# Rear_Logic.net
KiCad netlist of a schematic drawn in EAGLE
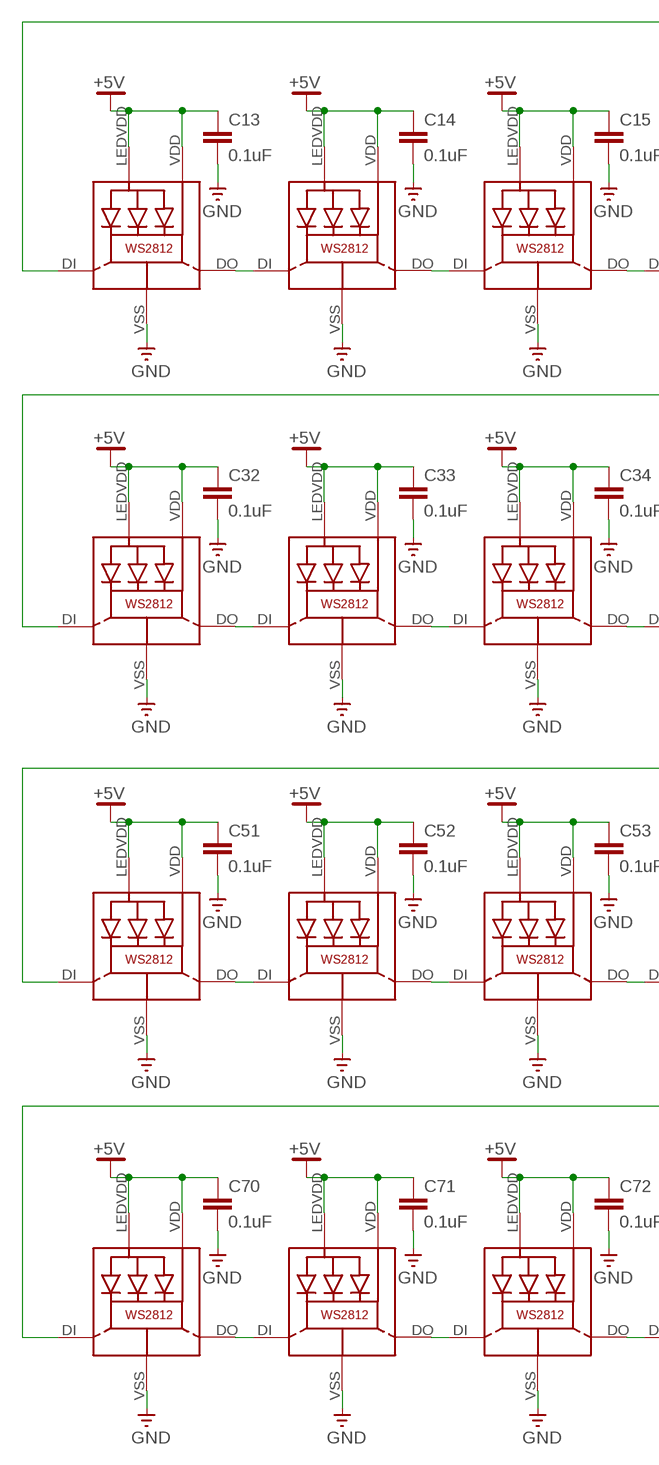
[diagram p0: schematic, sheet 1, part 1 of 2]
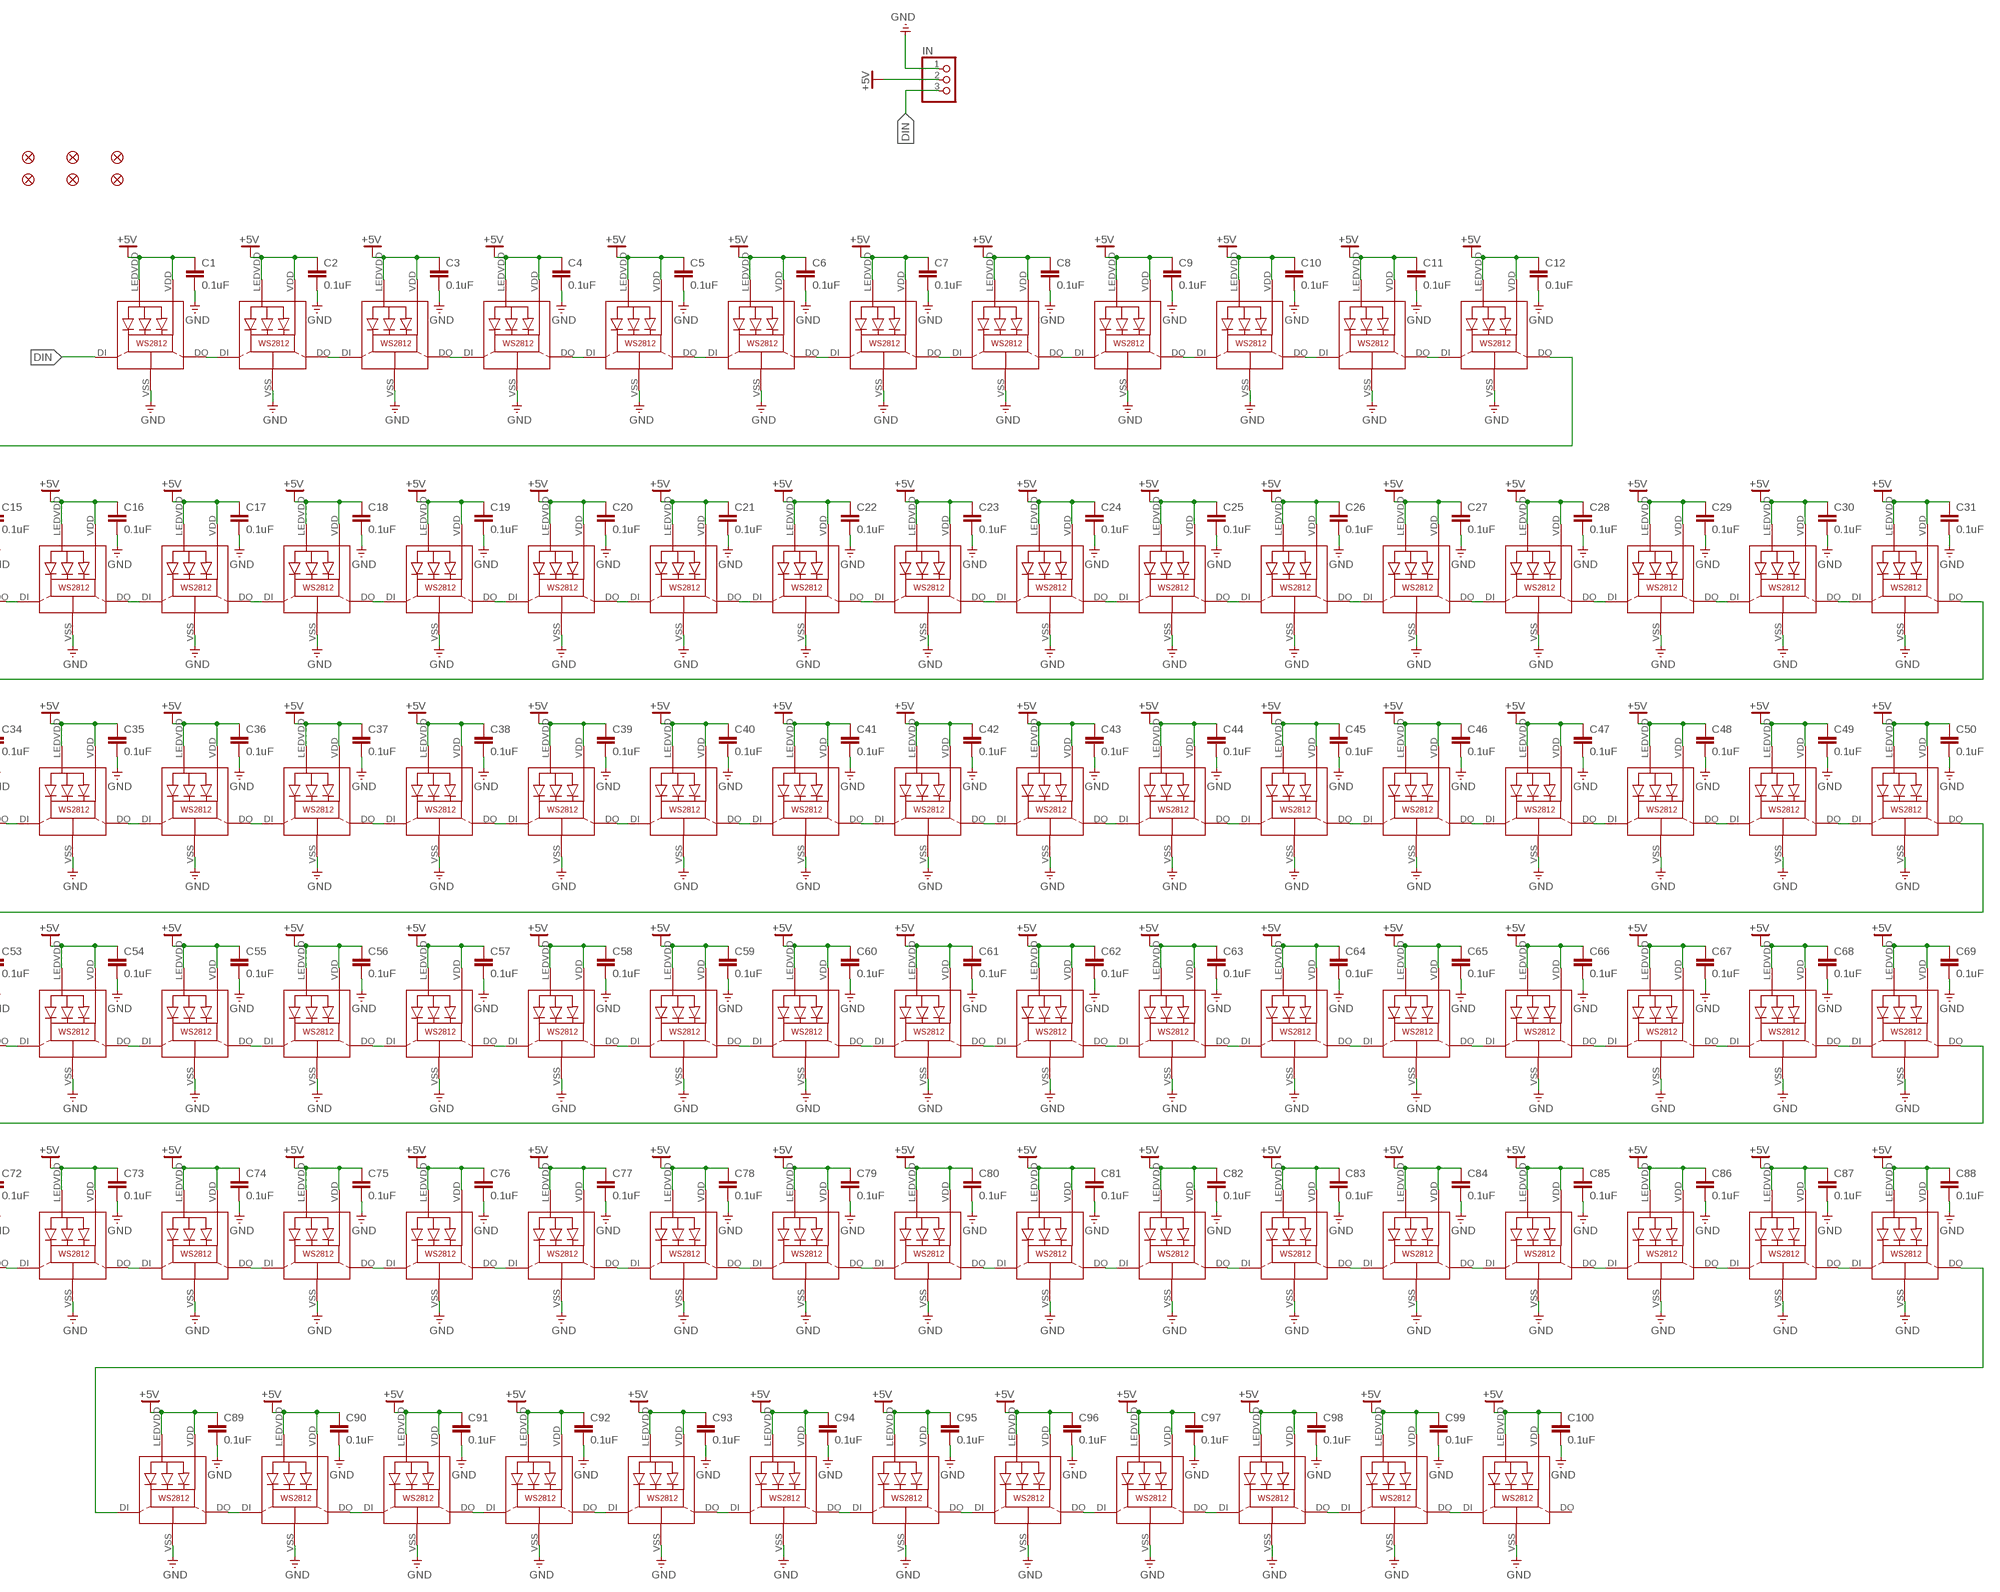
[diagram p1: schematic, sheet 1, part 2 of 2]

(export (version "E")
  (design (tool "Eeschema 10.0.6"))
  (components
    (comp (ref "C1")
      (value "0.1uF")
      (footprint "eagle-import:0805")
      (libsource (lib "eagle-import") (part "CAP0805"))
    )
    (comp (ref "C2")
      (value "0.1uF")
      (footprint "eagle-import:0805")
      (libsource (lib "eagle-import") (part "CAP0805"))
    )
    (comp (ref "C3")
      (value "0.1uF")
      (footprint "eagle-import:0805")
      (libsource (lib "eagle-import") (part "CAP0805"))
    )
    (comp (ref "C4")
      (value "0.1uF")
      (footprint "eagle-import:0805")
      (libsource (lib "eagle-import") (part "CAP0805"))
    )
    (comp (ref "C5")
      (value "0.1uF")
      (footprint "eagle-import:0805")
      (libsource (lib "eagle-import") (part "CAP0805"))
    )
    (comp (ref "C6")
      (value "0.1uF")
      (footprint "eagle-import:0805")
      (libsource (lib "eagle-import") (part "CAP0805"))
    )
    (comp (ref "C7")
      (value "0.1uF")
      (footprint "eagle-import:0805")
      (libsource (lib "eagle-import") (part "CAP0805"))
    )
    (comp (ref "C8")
      (value "0.1uF")
      (footprint "eagle-import:0805")
      (libsource (lib "eagle-import") (part "CAP0805"))
    )
    (comp (ref "C9")
      (value "0.1uF")
      (footprint "eagle-import:0805")
      (libsource (lib "eagle-import") (part "CAP0805"))
    )
    (comp (ref "C10")
      (value "0.1uF")
      (footprint "eagle-import:0805")
      (libsource (lib "eagle-import") (part "CAP0805"))
    )
    (comp (ref "C11")
      (value "0.1uF")
      (footprint "eagle-import:0805")
      (libsource (lib "eagle-import") (part "CAP0805"))
    )
    (comp (ref "C12")
      (value "0.1uF")
      (footprint "eagle-import:0805")
      (libsource (lib "eagle-import") (part "CAP0805"))
    )
    (comp (ref "C13")
      (value "0.1uF")
      (footprint "eagle-import:0805")
      (libsource (lib "eagle-import") (part "CAP0805"))
    )
    (comp (ref "C14")
      (value "0.1uF")
      (footprint "eagle-import:0805")
      (libsource (lib "eagle-import") (part "CAP0805"))
    )
    (comp (ref "C15")
      (value "0.1uF")
      (footprint "eagle-import:0805")
      (libsource (lib "eagle-import") (part "CAP0805"))
    )
    (comp (ref "C16")
      (value "0.1uF")
      (footprint "eagle-import:0805")
      (libsource (lib "eagle-import") (part "CAP0805"))
    )
    (comp (ref "C17")
      (value "0.1uF")
      (footprint "eagle-import:0805")
      (libsource (lib "eagle-import") (part "CAP0805"))
    )
    (comp (ref "C18")
      (value "0.1uF")
      (footprint "eagle-import:0805")
      (libsource (lib "eagle-import") (part "CAP0805"))
    )
    (comp (ref "C19")
      (value "0.1uF")
      (footprint "eagle-import:0805")
      (libsource (lib "eagle-import") (part "CAP0805"))
    )
    (comp (ref "C20")
      (value "0.1uF")
      (footprint "eagle-import:0805")
      (libsource (lib "eagle-import") (part "CAP0805"))
    )
    (comp (ref "C21")
      (value "0.1uF")
      (footprint "eagle-import:0805")
      (libsource (lib "eagle-import") (part "CAP0805"))
    )
    (comp (ref "C22")
      (value "0.1uF")
      (footprint "eagle-import:0805")
      (libsource (lib "eagle-import") (part "CAP0805"))
    )
    (comp (ref "C23")
      (value "0.1uF")
      (footprint "eagle-import:0805")
      (libsource (lib "eagle-import") (part "CAP0805"))
    )
    (comp (ref "C24")
      (value "0.1uF")
      (footprint "eagle-import:0805")
      (libsource (lib "eagle-import") (part "CAP0805"))
    )
    (comp (ref "C25")
      (value "0.1uF")
      (footprint "eagle-import:0805")
      (libsource (lib "eagle-import") (part "CAP0805"))
    )
    (comp (ref "C26")
      (value "0.1uF")
      (footprint "eagle-import:0805")
      (libsource (lib "eagle-import") (part "CAP0805"))
    )
    (comp (ref "C27")
      (value "0.1uF")
      (footprint "eagle-import:0805")
      (libsource (lib "eagle-import") (part "CAP0805"))
    )
    (comp (ref "C28")
      (value "0.1uF")
      (footprint "eagle-import:0805")
      (libsource (lib "eagle-import") (part "CAP0805"))
    )
    (comp (ref "C29")
      (value "0.1uF")
      (footprint "eagle-import:0805")
      (libsource (lib "eagle-import") (part "CAP0805"))
    )
    (comp (ref "C30")
      (value "0.1uF")
      (footprint "eagle-import:0805")
      (libsource (lib "eagle-import") (part "CAP0805"))
    )
    (comp (ref "C31")
      (value "0.1uF")
      (footprint "eagle-import:0805")
      (libsource (lib "eagle-import") (part "CAP0805"))
    )
    (comp (ref "C32")
      (value "0.1uF")
      (footprint "eagle-import:0805")
      (libsource (lib "eagle-import") (part "CAP0805"))
    )
    (comp (ref "C33")
      (value "0.1uF")
      (footprint "eagle-import:0805")
      (libsource (lib "eagle-import") (part "CAP0805"))
    )
    (comp (ref "C34")
      (value "0.1uF")
      (footprint "eagle-import:0805")
      (libsource (lib "eagle-import") (part "CAP0805"))
    )
    (comp (ref "C35")
      (value "0.1uF")
      (footprint "eagle-import:0805")
      (libsource (lib "eagle-import") (part "CAP0805"))
    )
    (comp (ref "C36")
      (value "0.1uF")
      (footprint "eagle-import:0805")
      (libsource (lib "eagle-import") (part "CAP0805"))
    )
    (comp (ref "C37")
      (value "0.1uF")
      (footprint "eagle-import:0805")
      (libsource (lib "eagle-import") (part "CAP0805"))
    )
    (comp (ref "C38")
      (value "0.1uF")
      (footprint "eagle-import:0805")
      (libsource (lib "eagle-import") (part "CAP0805"))
    )
    (comp (ref "C39")
      (value "0.1uF")
      (footprint "eagle-import:0805")
      (libsource (lib "eagle-import") (part "CAP0805"))
    )
    (comp (ref "C40")
      (value "0.1uF")
      (footprint "eagle-import:0805")
      (libsource (lib "eagle-import") (part "CAP0805"))
    )
    (comp (ref "C41")
      (value "0.1uF")
      (footprint "eagle-import:0805")
      (libsource (lib "eagle-import") (part "CAP0805"))
    )
    (comp (ref "C42")
      (value "0.1uF")
      (footprint "eagle-import:0805")
      (libsource (lib "eagle-import") (part "CAP0805"))
    )
    (comp (ref "C43")
      (value "0.1uF")
      (footprint "eagle-import:0805")
      (libsource (lib "eagle-import") (part "CAP0805"))
    )
    (comp (ref "C44")
      (value "0.1uF")
      (footprint "eagle-import:0805")
      (libsource (lib "eagle-import") (part "CAP0805"))
    )
    (comp (ref "C45")
      (value "0.1uF")
      (footprint "eagle-import:0805")
      (libsource (lib "eagle-import") (part "CAP0805"))
    )
    (comp (ref "C46")
      (value "0.1uF")
      (footprint "eagle-import:0805")
      (libsource (lib "eagle-import") (part "CAP0805"))
    )
    (comp (ref "C47")
      (value "0.1uF")
      (footprint "eagle-import:0805")
      (libsource (lib "eagle-import") (part "CAP0805"))
    )
    (comp (ref "C48")
      (value "0.1uF")
      (footprint "eagle-import:0805")
      (libsource (lib "eagle-import") (part "CAP0805"))
    )
    (comp (ref "C49")
      (value "0.1uF")
      (footprint "eagle-import:0805")
      (libsource (lib "eagle-import") (part "CAP0805"))
    )
    (comp (ref "C50")
      (value "0.1uF")
      (footprint "eagle-import:0805")
      (libsource (lib "eagle-import") (part "CAP0805"))
    )
    (comp (ref "C51")
      (value "0.1uF")
      (footprint "eagle-import:0805")
      (libsource (lib "eagle-import") (part "CAP0805"))
    )
    (comp (ref "C52")
      (value "0.1uF")
      (footprint "eagle-import:0805")
      (libsource (lib "eagle-import") (part "CAP0805"))
    )
    (comp (ref "C53")
      (value "0.1uF")
      (footprint "eagle-import:0805")
      (libsource (lib "eagle-import") (part "CAP0805"))
    )
    (comp (ref "C54")
      (value "0.1uF")
      (footprint "eagle-import:0805")
      (libsource (lib "eagle-import") (part "CAP0805"))
    )
    (comp (ref "C55")
      (value "0.1uF")
      (footprint "eagle-import:0805")
      (libsource (lib "eagle-import") (part "CAP0805"))
    )
    (comp (ref "C56")
      (value "0.1uF")
      (footprint "eagle-import:0805")
      (libsource (lib "eagle-import") (part "CAP0805"))
    )
    (comp (ref "C57")
      (value "0.1uF")
      (footprint "eagle-import:0805")
      (libsource (lib "eagle-import") (part "CAP0805"))
    )
    (comp (ref "C58")
      (value "0.1uF")
      (footprint "eagle-import:0805")
      (libsource (lib "eagle-import") (part "CAP0805"))
    )
    (comp (ref "C59")
      (value "0.1uF")
      (footprint "eagle-import:0805")
      (libsource (lib "eagle-import") (part "CAP0805"))
    )
    (comp (ref "C60")
      (value "0.1uF")
      (footprint "eagle-import:0805")
      (libsource (lib "eagle-import") (part "CAP0805"))
    )
    (comp (ref "C61")
      (value "0.1uF")
      (footprint "eagle-import:0805")
      (libsource (lib "eagle-import") (part "CAP0805"))
    )
    (comp (ref "C62")
      (value "0.1uF")
      (footprint "eagle-import:0805")
      (libsource (lib "eagle-import") (part "CAP0805"))
    )
    (comp (ref "C63")
      (value "0.1uF")
      (footprint "eagle-import:0805")
      (libsource (lib "eagle-import") (part "CAP0805"))
    )
    (comp (ref "C64")
      (value "0.1uF")
      (footprint "eagle-import:0805")
      (libsource (lib "eagle-import") (part "CAP0805"))
    )
    (comp (ref "C65")
      (value "0.1uF")
      (footprint "eagle-import:0805")
      (libsource (lib "eagle-import") (part "CAP0805"))
    )
    (comp (ref "C66")
      (value "0.1uF")
      (footprint "eagle-import:0805")
      (libsource (lib "eagle-import") (part "CAP0805"))
    )
    (comp (ref "C67")
      (value "0.1uF")
      (footprint "eagle-import:0805")
      (libsource (lib "eagle-import") (part "CAP0805"))
    )
    (comp (ref "C68")
      (value "0.1uF")
      (footprint "eagle-import:0805")
      (libsource (lib "eagle-import") (part "CAP0805"))
    )
    (comp (ref "C69")
      (value "0.1uF")
      (footprint "eagle-import:0805")
      (libsource (lib "eagle-import") (part "CAP0805"))
    )
    (comp (ref "C70")
      (value "0.1uF")
      (footprint "eagle-import:0805")
      (libsource (lib "eagle-import") (part "CAP0805"))
    )
    (comp (ref "C71")
      (value "0.1uF")
      (footprint "eagle-import:0805")
      (libsource (lib "eagle-import") (part "CAP0805"))
    )
    (comp (ref "C72")
      (value "0.1uF")
      (footprint "eagle-import:0805")
      (libsource (lib "eagle-import") (part "CAP0805"))
    )
    (comp (ref "C73")
      (value "0.1uF")
      (footprint "eagle-import:0805")
      (libsource (lib "eagle-import") (part "CAP0805"))
    )
    (comp (ref "C74")
      (value "0.1uF")
      (footprint "eagle-import:0805")
      (libsource (lib "eagle-import") (part "CAP0805"))
    )
    (comp (ref "C75")
      (value "0.1uF")
      (footprint "eagle-import:0805")
      (libsource (lib "eagle-import") (part "CAP0805"))
    )
    (comp (ref "C76")
      (value "0.1uF")
      (footprint "eagle-import:0805")
      (libsource (lib "eagle-import") (part "CAP0805"))
    )
    (comp (ref "C77")
      (value "0.1uF")
      (footprint "eagle-import:0805")
      (libsource (lib "eagle-import") (part "CAP0805"))
    )
    (comp (ref "C78")
      (value "0.1uF")
      (footprint "eagle-import:0805")
      (libsource (lib "eagle-import") (part "CAP0805"))
    )
    (comp (ref "C79")
      (value "0.1uF")
      (footprint "eagle-import:0805")
      (libsource (lib "eagle-import") (part "CAP0805"))
    )
    (comp (ref "C80")
      (value "0.1uF")
      (footprint "eagle-import:0805")
      (libsource (lib "eagle-import") (part "CAP0805"))
    )
    (comp (ref "C81")
      (value "0.1uF")
      (footprint "eagle-import:0805")
      (libsource (lib "eagle-import") (part "CAP0805"))
    )
    (comp (ref "C82")
      (value "0.1uF")
      (footprint "eagle-import:0805")
      (libsource (lib "eagle-import") (part "CAP0805"))
    )
    (comp (ref "C83")
      (value "0.1uF")
      (footprint "eagle-import:0805")
      (libsource (lib "eagle-import") (part "CAP0805"))
    )
    (comp (ref "C84")
      (value "0.1uF")
      (footprint "eagle-import:0805")
      (libsource (lib "eagle-import") (part "CAP0805"))
    )
    (comp (ref "C85")
      (value "0.1uF")
      (footprint "eagle-import:0805")
      (libsource (lib "eagle-import") (part "CAP0805"))
    )
    (comp (ref "C86")
      (value "0.1uF")
      (footprint "eagle-import:0805")
      (libsource (lib "eagle-import") (part "CAP0805"))
    )
    (comp (ref "C87")
      (value "0.1uF")
      (footprint "eagle-import:0805")
      (libsource (lib "eagle-import") (part "CAP0805"))
    )
    (comp (ref "C88")
      (value "0.1uF")
      (footprint "eagle-import:0805")
      (libsource (lib "eagle-import") (part "CAP0805"))
    )
    (comp (ref "C89")
      (value "0.1uF")
      (footprint "eagle-import:0805")
      (libsource (lib "eagle-import") (part "CAP0805"))
    )
    (comp (ref "C90")
      (value "0.1uF")
      (footprint "eagle-import:0805")
      (libsource (lib "eagle-import") (part "CAP0805"))
    )
    (comp (ref "C91")
      (value "0.1uF")
      (footprint "eagle-import:0805")
      (libsource (lib "eagle-import") (part "CAP0805"))
    )
    (comp (ref "C92")
      (value "0.1uF")
      (footprint "eagle-import:0805")
      (libsource (lib "eagle-import") (part "CAP0805"))
    )
    (comp (ref "C93")
      (value "0.1uF")
      (footprint "eagle-import:0805")
      (libsource (lib "eagle-import") (part "CAP0805"))
    )
    (comp (ref "C94")
      (value "0.1uF")
      (footprint "eagle-import:0805")
      (libsource (lib "eagle-import") (part "CAP0805"))
    )
    (comp (ref "C95")
      (value "0.1uF")
      (footprint "eagle-import:0805")
      (libsource (lib "eagle-import") (part "CAP0805"))
    )
    (comp (ref "C96")
      (value "0.1uF")
      (footprint "eagle-import:0805")
      (libsource (lib "eagle-import") (part "CAP0805"))
    )
    (comp (ref "C97")
      (value "0.1uF")
      (footprint "eagle-import:0805")
      (libsource (lib "eagle-import") (part "CAP0805"))
    )
    (comp (ref "C98")
      (value "0.1uF")
      (footprint "eagle-import:0805")
      (libsource (lib "eagle-import") (part "CAP0805"))
    )
    (comp (ref "C99")
      (value "0.1uF")
      (footprint "eagle-import:0805")
      (libsource (lib "eagle-import") (part "CAP0805"))
    )
    (comp (ref "C100")
      (value "0.1uF")
      (footprint "eagle-import:0805")
      (libsource (lib "eagle-import") (part "CAP0805"))
    )
    (comp (ref "FID1")
      (value "FIDUCIAL1.5X3")
      (footprint "eagle-import:FIDUCIAL-1.5X3")
      (libsource (lib "eagle-import") (part "FIDUCIAL1.5X3"))
    )
    (comp (ref "FID2")
      (value "FIDUCIAL1.5X3")
      (footprint "eagle-import:FIDUCIAL-1.5X3")
      (libsource (lib "eagle-import") (part "FIDUCIAL1.5X3"))
    )
    (comp (ref "FID3")
      (value "FIDUCIAL1.5X3")
      (footprint "eagle-import:FIDUCIAL-1.5X3")
      (libsource (lib "eagle-import") (part "FIDUCIAL1.5X3"))
    )
    (comp (ref "FID4")
      (value "FIDUCIAL1.5X3")
      (footprint "eagle-import:FIDUCIAL-1.5X3")
      (libsource (lib "eagle-import") (part "FIDUCIAL1.5X3"))
    )
    (comp (ref "FID5")
      (value "FIDUCIAL1.5X3")
      (footprint "eagle-import:FIDUCIAL-1.5X3")
      (libsource (lib "eagle-import") (part "FIDUCIAL1.5X3"))
    )
    (comp (ref "FID6")
      (value "FIDUCIAL1.5X3")
      (footprint "eagle-import:FIDUCIAL-1.5X3")
      (libsource (lib "eagle-import") (part "FIDUCIAL1.5X3"))
    )
    (comp (ref "IN")
      (value "PINHD-1X3")
      (footprint "eagle-import:1X03")
      (libsource (lib "eagle-import") (part "PINHD-1X3"))
    )
    (comp (ref "LED1")
      (value "WS2812")
      (footprint "eagle-import:WS2812")
      (libsource (lib "eagle-import") (part "WS2812"))
    )
    (comp (ref "LED2")
      (value "WS2812")
      (footprint "eagle-import:WS2812")
      (libsource (lib "eagle-import") (part "WS2812"))
    )
    (comp (ref "LED3")
      (value "WS2812")
      (footprint "eagle-import:WS2812")
      (libsource (lib "eagle-import") (part "WS2812"))
    )
    (comp (ref "LED4")
      (value "WS2812")
      (footprint "eagle-import:WS2812")
      (libsource (lib "eagle-import") (part "WS2812"))
    )
    (comp (ref "LED5")
      (value "WS2812")
      (footprint "eagle-import:WS2812")
      (libsource (lib "eagle-import") (part "WS2812"))
    )
    (comp (ref "LED6")
      (value "WS2812")
      (footprint "eagle-import:WS2812")
      (libsource (lib "eagle-import") (part "WS2812"))
    )
    (comp (ref "LED7")
      (value "WS2812")
      (footprint "eagle-import:WS2812")
      (libsource (lib "eagle-import") (part "WS2812"))
    )
    (comp (ref "LED8")
      (value "WS2812")
      (footprint "eagle-import:WS2812")
      (libsource (lib "eagle-import") (part "WS2812"))
    )
    (comp (ref "LED9")
      (value "WS2812")
      (footprint "eagle-import:WS2812")
      (libsource (lib "eagle-import") (part "WS2812"))
    )
    (comp (ref "LED10")
      (value "WS2812")
      (footprint "eagle-import:WS2812")
      (libsource (lib "eagle-import") (part "WS2812"))
    )
    (comp (ref "LED11")
      (value "WS2812")
      (footprint "eagle-import:WS2812")
      (libsource (lib "eagle-import") (part "WS2812"))
    )
    (comp (ref "LED12")
      (value "WS2812")
      (footprint "eagle-import:WS2812")
      (libsource (lib "eagle-import") (part "WS2812"))
    )
    (comp (ref "LED13")
      (value "WS2812")
      (footprint "eagle-import:WS2812")
      (libsource (lib "eagle-import") (part "WS2812"))
    )
    (comp (ref "LED14")
      (value "WS2812")
      (footprint "eagle-import:WS2812")
      (libsource (lib "eagle-import") (part "WS2812"))
    )
    (comp (ref "LED15")
      (value "WS2812")
      (footprint "eagle-import:WS2812")
      (libsource (lib "eagle-import") (part "WS2812"))
    )
    (comp (ref "LED16")
      (value "WS2812")
      (footprint "eagle-import:WS2812")
      (libsource (lib "eagle-import") (part "WS2812"))
    )
    (comp (ref "LED17")
      (value "WS2812")
      (footprint "eagle-import:WS2812")
      (libsource (lib "eagle-import") (part "WS2812"))
    )
    (comp (ref "LED18")
      (value "WS2812")
      (footprint "eagle-import:WS2812")
      (libsource (lib "eagle-import") (part "WS2812"))
    )
    (comp (ref "LED19")
      (value "WS2812")
      (footprint "eagle-import:WS2812")
      (libsource (lib "eagle-import") (part "WS2812"))
    )
    (comp (ref "LED20")
      (value "WS2812")
      (footprint "eagle-import:WS2812")
      (libsource (lib "eagle-import") (part "WS2812"))
    )
    (comp (ref "LED21")
      (value "WS2812")
      (footprint "eagle-import:WS2812")
      (libsource (lib "eagle-import") (part "WS2812"))
    )
    (comp (ref "LED22")
      (value "WS2812")
      (footprint "eagle-import:WS2812")
      (libsource (lib "eagle-import") (part "WS2812"))
    )
    (comp (ref "LED23")
      (value "WS2812")
      (footprint "eagle-import:WS2812")
      (libsource (lib "eagle-import") (part "WS2812"))
    )
    (comp (ref "LED24")
      (value "WS2812")
      (footprint "eagle-import:WS2812")
      (libsource (lib "eagle-import") (part "WS2812"))
    )
    (comp (ref "LED25")
      (value "WS2812")
      (footprint "eagle-import:WS2812")
      (libsource (lib "eagle-import") (part "WS2812"))
    )
    (comp (ref "LED26")
      (value "WS2812")
      (footprint "eagle-import:WS2812")
      (libsource (lib "eagle-import") (part "WS2812"))
    )
    (comp (ref "LED27")
      (value "WS2812")
      (footprint "eagle-import:WS2812")
      (libsource (lib "eagle-import") (part "WS2812"))
    )
    (comp (ref "LED28")
      (value "WS2812")
      (footprint "eagle-import:WS2812")
      (libsource (lib "eagle-import") (part "WS2812"))
    )
    (comp (ref "LED29")
      (value "WS2812")
      (footprint "eagle-import:WS2812")
      (libsource (lib "eagle-import") (part "WS2812"))
    )
    (comp (ref "LED30")
      (value "WS2812")
      (footprint "eagle-import:WS2812")
      (libsource (lib "eagle-import") (part "WS2812"))
    )
    (comp (ref "LED31")
      (value "WS2812")
      (footprint "eagle-import:WS2812")
      (libsource (lib "eagle-import") (part "WS2812"))
    )
    (comp (ref "LED32")
      (value "WS2812")
      (footprint "eagle-import:WS2812")
      (libsource (lib "eagle-import") (part "WS2812"))
    )
    (comp (ref "LED33")
      (value "WS2812")
      (footprint "eagle-import:WS2812")
      (libsource (lib "eagle-import") (part "WS2812"))
    )
    (comp (ref "LED34")
      (value "WS2812")
      (footprint "eagle-import:WS2812")
      (libsource (lib "eagle-import") (part "WS2812"))
    )
    (comp (ref "LED35")
      (value "WS2812")
      (footprint "eagle-import:WS2812")
      (libsource (lib "eagle-import") (part "WS2812"))
    )
    (comp (ref "LED36")
      (value "WS2812")
      (footprint "eagle-import:WS2812")
      (libsource (lib "eagle-import") (part "WS2812"))
    )
    (comp (ref "LED37")
      (value "WS2812")
      (footprint "eagle-import:WS2812")
      (libsource (lib "eagle-import") (part "WS2812"))
    )
    (comp (ref "LED38")
      (value "WS2812")
      (footprint "eagle-import:WS2812")
      (libsource (lib "eagle-import") (part "WS2812"))
    )
    (comp (ref "LED39")
      (value "WS2812")
      (footprint "eagle-import:WS2812")
      (libsource (lib "eagle-import") (part "WS2812"))
    )
    (comp (ref "LED40")
      (value "WS2812")
      (footprint "eagle-import:WS2812")
      (libsource (lib "eagle-import") (part "WS2812"))
    )
    (comp (ref "LED41")
      (value "WS2812")
      (footprint "eagle-import:WS2812")
      (libsource (lib "eagle-import") (part "WS2812"))
    )
    (comp (ref "LED42")
      (value "WS2812")
      (footprint "eagle-import:WS2812")
      (libsource (lib "eagle-import") (part "WS2812"))
    )
    (comp (ref "LED43")
      (value "WS2812")
      (footprint "eagle-import:WS2812")
      (libsource (lib "eagle-import") (part "WS2812"))
    )
    (comp (ref "LED44")
      (value "WS2812")
      (footprint "eagle-import:WS2812")
      (libsource (lib "eagle-import") (part "WS2812"))
    )
    (comp (ref "LED45")
      (value "WS2812")
      (footprint "eagle-import:WS2812")
      (libsource (lib "eagle-import") (part "WS2812"))
    )
    (comp (ref "LED46")
      (value "WS2812")
      (footprint "eagle-import:WS2812")
      (libsource (lib "eagle-import") (part "WS2812"))
    )
    (comp (ref "LED47")
      (value "WS2812")
      (footprint "eagle-import:WS2812")
      (libsource (lib "eagle-import") (part "WS2812"))
    )
    (comp (ref "LED48")
      (value "WS2812")
      (footprint "eagle-import:WS2812")
      (libsource (lib "eagle-import") (part "WS2812"))
    )
    (comp (ref "LED49")
      (value "WS2812")
      (footprint "eagle-import:WS2812")
      (libsource (lib "eagle-import") (part "WS2812"))
    )
    (comp (ref "LED50")
      (value "WS2812")
      (footprint "eagle-import:WS2812")
      (libsource (lib "eagle-import") (part "WS2812"))
    )
    (comp (ref "LED51")
      (value "WS2812")
      (footprint "eagle-import:WS2812")
      (libsource (lib "eagle-import") (part "WS2812"))
    )
    (comp (ref "LED52")
      (value "WS2812")
      (footprint "eagle-import:WS2812")
      (libsource (lib "eagle-import") (part "WS2812"))
    )
    (comp (ref "LED53")
      (value "WS2812")
      (footprint "eagle-import:WS2812")
      (libsource (lib "eagle-import") (part "WS2812"))
    )
    (comp (ref "LED54")
      (value "WS2812")
      (footprint "eagle-import:WS2812")
      (libsource (lib "eagle-import") (part "WS2812"))
    )
    (comp (ref "LED55")
      (value "WS2812")
      (footprint "eagle-import:WS2812")
      (libsource (lib "eagle-import") (part "WS2812"))
    )
    (comp (ref "LED56")
      (value "WS2812")
      (footprint "eagle-import:WS2812")
      (libsource (lib "eagle-import") (part "WS2812"))
    )
    (comp (ref "LED57")
      (value "WS2812")
      (footprint "eagle-import:WS2812")
      (libsource (lib "eagle-import") (part "WS2812"))
    )
    (comp (ref "LED58")
      (value "WS2812")
      (footprint "eagle-import:WS2812")
      (libsource (lib "eagle-import") (part "WS2812"))
    )
    (comp (ref "LED59")
      (value "WS2812")
      (footprint "eagle-import:WS2812")
      (libsource (lib "eagle-import") (part "WS2812"))
    )
    (comp (ref "LED60")
      (value "WS2812")
      (footprint "eagle-import:WS2812")
      (libsource (lib "eagle-import") (part "WS2812"))
    )
    (comp (ref "LED61")
      (value "WS2812")
      (footprint "eagle-import:WS2812")
      (libsource (lib "eagle-import") (part "WS2812"))
    )
    (comp (ref "LED62")
      (value "WS2812")
      (footprint "eagle-import:WS2812")
      (libsource (lib "eagle-import") (part "WS2812"))
    )
    (comp (ref "LED63")
      (value "WS2812")
      (footprint "eagle-import:WS2812")
      (libsource (lib "eagle-import") (part "WS2812"))
    )
    (comp (ref "LED64")
      (value "WS2812")
      (footprint "eagle-import:WS2812")
      (libsource (lib "eagle-import") (part "WS2812"))
    )
    (comp (ref "LED65")
      (value "WS2812")
      (footprint "eagle-import:WS2812")
      (libsource (lib "eagle-import") (part "WS2812"))
    )
    (comp (ref "LED66")
      (value "WS2812")
      (footprint "eagle-import:WS2812")
      (libsource (lib "eagle-import") (part "WS2812"))
    )
    (comp (ref "LED67")
      (value "WS2812")
      (footprint "eagle-import:WS2812")
      (libsource (lib "eagle-import") (part "WS2812"))
    )
    (comp (ref "LED68")
      (value "WS2812")
      (footprint "eagle-import:WS2812")
      (libsource (lib "eagle-import") (part "WS2812"))
    )
    (comp (ref "LED69")
      (value "WS2812")
      (footprint "eagle-import:WS2812")
      (libsource (lib "eagle-import") (part "WS2812"))
    )
    (comp (ref "LED70")
      (value "WS2812")
      (footprint "eagle-import:WS2812")
      (libsource (lib "eagle-import") (part "WS2812"))
    )
    (comp (ref "LED71")
      (value "WS2812")
      (footprint "eagle-import:WS2812")
      (libsource (lib "eagle-import") (part "WS2812"))
    )
    (comp (ref "LED72")
      (value "WS2812")
      (footprint "eagle-import:WS2812")
      (libsource (lib "eagle-import") (part "WS2812"))
    )
    (comp (ref "LED73")
      (value "WS2812")
      (footprint "eagle-import:WS2812")
      (libsource (lib "eagle-import") (part "WS2812"))
    )
    (comp (ref "LED74")
      (value "WS2812")
      (footprint "eagle-import:WS2812")
      (libsource (lib "eagle-import") (part "WS2812"))
    )
    (comp (ref "LED75")
      (value "WS2812")
      (footprint "eagle-import:WS2812")
      (libsource (lib "eagle-import") (part "WS2812"))
    )
    (comp (ref "LED76")
      (value "WS2812")
      (footprint "eagle-import:WS2812")
      (libsource (lib "eagle-import") (part "WS2812"))
    )
    (comp (ref "LED77")
      (value "WS2812")
      (footprint "eagle-import:WS2812")
      (libsource (lib "eagle-import") (part "WS2812"))
    )
    (comp (ref "LED78")
      (value "WS2812")
      (footprint "eagle-import:WS2812")
      (libsource (lib "eagle-import") (part "WS2812"))
    )
    (comp (ref "LED79")
      (value "WS2812")
      (footprint "eagle-import:WS2812")
      (libsource (lib "eagle-import") (part "WS2812"))
    )
    (comp (ref "LED80")
      (value "WS2812")
      (footprint "eagle-import:WS2812")
      (libsource (lib "eagle-import") (part "WS2812"))
    )
    (comp (ref "LED81")
      (value "WS2812")
      (footprint "eagle-import:WS2812")
      (libsource (lib "eagle-import") (part "WS2812"))
    )
    (comp (ref "LED82")
      (value "WS2812")
      (footprint "eagle-import:WS2812")
      (libsource (lib "eagle-import") (part "WS2812"))
    )
    (comp (ref "LED83")
      (value "WS2812")
      (footprint "eagle-import:WS2812")
      (libsource (lib "eagle-import") (part "WS2812"))
    )
    (comp (ref "LED84")
      (value "WS2812")
      (footprint "eagle-import:WS2812")
      (libsource (lib "eagle-import") (part "WS2812"))
    )
    (comp (ref "LED85")
      (value "WS2812")
      (footprint "eagle-import:WS2812")
      (libsource (lib "eagle-import") (part "WS2812"))
    )
    (comp (ref "LED86")
      (value "WS2812")
      (footprint "eagle-import:WS2812")
      (libsource (lib "eagle-import") (part "WS2812"))
    )
    (comp (ref "LED87")
      (value "WS2812")
      (footprint "eagle-import:WS2812")
      (libsource (lib "eagle-import") (part "WS2812"))
    )
    (comp (ref "LED88")
      (value "WS2812")
      (footprint "eagle-import:WS2812")
      (libsource (lib "eagle-import") (part "WS2812"))
    )
    (comp (ref "LED89")
      (value "WS2812")
      (footprint "eagle-import:WS2812")
      (libsource (lib "eagle-import") (part "WS2812"))
    )
    (comp (ref "LED90")
      (value "WS2812")
      (footprint "eagle-import:WS2812")
      (libsource (lib "eagle-import") (part "WS2812"))
    )
    (comp (ref "LED91")
      (value "WS2812")
      (footprint "eagle-import:WS2812")
      (libsource (lib "eagle-import") (part "WS2812"))
    )
    (comp (ref "LED92")
      (value "WS2812")
      (footprint "eagle-import:WS2812")
      (libsource (lib "eagle-import") (part "WS2812"))
    )
    (comp (ref "LED93")
      (value "WS2812")
      (footprint "eagle-import:WS2812")
      (libsource (lib "eagle-import") (part "WS2812"))
    )
    (comp (ref "LED94")
      (value "WS2812")
      (footprint "eagle-import:WS2812")
      (libsource (lib "eagle-import") (part "WS2812"))
    )
    (comp (ref "LED95")
      (value "WS2812")
      (footprint "eagle-import:WS2812")
      (libsource (lib "eagle-import") (part "WS2812"))
    )
    (comp (ref "LED96")
      (value "WS2812")
      (footprint "eagle-import:WS2812")
      (libsource (lib "eagle-import") (part "WS2812"))
    )
    (comp (ref "LED97")
      (value "WS2812")
      (footprint "eagle-import:WS2812")
      (libsource (lib "eagle-import") (part "WS2812"))
    )
    (comp (ref "LED98")
      (value "WS2812")
      (footprint "eagle-import:WS2812")
      (libsource (lib "eagle-import") (part "WS2812"))
    )
    (comp (ref "LED99")
      (value "WS2812")
      (footprint "eagle-import:WS2812")
      (libsource (lib "eagle-import") (part "WS2812"))
    )
    (comp (ref "LED100")
      (value "WS2812")
      (footprint "eagle-import:WS2812")
      (libsource (lib "eagle-import") (part "WS2812"))
    )
  )
  (nets
    (net (code "1") (name "+5V") (class "Default")
      (node (ref "C1") (pin "1") (pinfunction "1_1") (pintype "passive"))
      (node (ref "C10") (pin "1") (pinfunction "1_1") (pintype "passive"))
      (node (ref "C100") (pin "1") (pinfunction "1_1") (pintype "passive"))
      (node (ref "C11") (pin "1") (pinfunction "1_1") (pintype "passive"))
      (node (ref "C12") (pin "1") (pinfunction "1_1") (pintype "passive"))
      (node (ref "C13") (pin "1") (pinfunction "1_1") (pintype "passive"))
      (node (ref "C14") (pin "1") (pinfunction "1_1") (pintype "passive"))
      (node (ref "C15") (pin "1") (pinfunction "1_1") (pintype "passive"))
      (node (ref "C16") (pin "1") (pinfunction "1_1") (pintype "passive"))
      (node (ref "C17") (pin "1") (pinfunction "1_1") (pintype "passive"))
      (node (ref "C18") (pin "1") (pinfunction "1_1") (pintype "passive"))
      (node (ref "C19") (pin "1") (pinfunction "1_1") (pintype "passive"))
      (node (ref "C2") (pin "1") (pinfunction "1_1") (pintype "passive"))
      (node (ref "C20") (pin "1") (pinfunction "1_1") (pintype "passive"))
      (node (ref "C21") (pin "1") (pinfunction "1_1") (pintype "passive"))
      (node (ref "C22") (pin "1") (pinfunction "1_1") (pintype "passive"))
      (node (ref "C23") (pin "1") (pinfunction "1_1") (pintype "passive"))
      (node (ref "C24") (pin "1") (pinfunction "1_1") (pintype "passive"))
      (node (ref "C25") (pin "1") (pinfunction "1_1") (pintype "passive"))
      (node (ref "C26") (pin "1") (pinfunction "1_1") (pintype "passive"))
      (node (ref "C27") (pin "1") (pinfunction "1_1") (pintype "passive"))
      (node (ref "C28") (pin "1") (pinfunction "1_1") (pintype "passive"))
      (node (ref "C29") (pin "1") (pinfunction "1_1") (pintype "passive"))
      (node (ref "C3") (pin "1") (pinfunction "1_1") (pintype "passive"))
      (node (ref "C30") (pin "1") (pinfunction "1_1") (pintype "passive"))
      (node (ref "C31") (pin "1") (pinfunction "1_1") (pintype "passive"))
      (node (ref "C32") (pin "1") (pinfunction "1_1") (pintype "passive"))
      (node (ref "C33") (pin "1") (pinfunction "1_1") (pintype "passive"))
      (node (ref "C34") (pin "1") (pinfunction "1_1") (pintype "passive"))
      (node (ref "C35") (pin "1") (pinfunction "1_1") (pintype "passive"))
      (node (ref "C36") (pin "1") (pinfunction "1_1") (pintype "passive"))
      (node (ref "C37") (pin "1") (pinfunction "1_1") (pintype "passive"))
      (node (ref "C38") (pin "1") (pinfunction "1_1") (pintype "passive"))
      (node (ref "C39") (pin "1") (pinfunction "1_1") (pintype "passive"))
      (node (ref "C4") (pin "1") (pinfunction "1_1") (pintype "passive"))
      (node (ref "C40") (pin "1") (pinfunction "1_1") (pintype "passive"))
      (node (ref "C41") (pin "1") (pinfunction "1_1") (pintype "passive"))
      (node (ref "C42") (pin "1") (pinfunction "1_1") (pintype "passive"))
      (node (ref "C43") (pin "1") (pinfunction "1_1") (pintype "passive"))
      (node (ref "C44") (pin "1") (pinfunction "1_1") (pintype "passive"))
      (node (ref "C45") (pin "1") (pinfunction "1_1") (pintype "passive"))
      (node (ref "C46") (pin "1") (pinfunction "1_1") (pintype "passive"))
      (node (ref "C47") (pin "1") (pinfunction "1_1") (pintype "passive"))
      (node (ref "C48") (pin "1") (pinfunction "1_1") (pintype "passive"))
      (node (ref "C49") (pin "1") (pinfunction "1_1") (pintype "passive"))
      (node (ref "C5") (pin "1") (pinfunction "1_1") (pintype "passive"))
      (node (ref "C50") (pin "1") (pinfunction "1_1") (pintype "passive"))
      (node (ref "C51") (pin "1") (pinfunction "1_1") (pintype "passive"))
      (node (ref "C52") (pin "1") (pinfunction "1_1") (pintype "passive"))
      (node (ref "C53") (pin "1") (pinfunction "1_1") (pintype "passive"))
      (node (ref "C54") (pin "1") (pinfunction "1_1") (pintype "passive"))
      (node (ref "C55") (pin "1") (pinfunction "1_1") (pintype "passive"))
      (node (ref "C56") (pin "1") (pinfunction "1_1") (pintype "passive"))
      (node (ref "C57") (pin "1") (pinfunction "1_1") (pintype "passive"))
      (node (ref "C58") (pin "1") (pinfunction "1_1") (pintype "passive"))
      (node (ref "C59") (pin "1") (pinfunction "1_1") (pintype "passive"))
      (node (ref "C6") (pin "1") (pinfunction "1_1") (pintype "passive"))
      (node (ref "C60") (pin "1") (pinfunction "1_1") (pintype "passive"))
      (node (ref "C61") (pin "1") (pinfunction "1_1") (pintype "passive"))
      (node (ref "C62") (pin "1") (pinfunction "1_1") (pintype "passive"))
      (node (ref "C63") (pin "1") (pinfunction "1_1") (pintype "passive"))
      (node (ref "C64") (pin "1") (pinfunction "1_1") (pintype "passive"))
      (node (ref "C65") (pin "1") (pinfunction "1_1") (pintype "passive"))
      (node (ref "C66") (pin "1") (pinfunction "1_1") (pintype "passive"))
      (node (ref "C67") (pin "1") (pinfunction "1_1") (pintype "passive"))
      (node (ref "C68") (pin "1") (pinfunction "1_1") (pintype "passive"))
      (node (ref "C69") (pin "1") (pinfunction "1_1") (pintype "passive"))
      (node (ref "C7") (pin "1") (pinfunction "1_1") (pintype "passive"))
      (node (ref "C70") (pin "1") (pinfunction "1_1") (pintype "passive"))
      (node (ref "C71") (pin "1") (pinfunction "1_1") (pintype "passive"))
      (node (ref "C72") (pin "1") (pinfunction "1_1") (pintype "passive"))
      (node (ref "C73") (pin "1") (pinfunction "1_1") (pintype "passive"))
      (node (ref "C74") (pin "1") (pinfunction "1_1") (pintype "passive"))
      (node (ref "C75") (pin "1") (pinfunction "1_1") (pintype "passive"))
      (node (ref "C76") (pin "1") (pinfunction "1_1") (pintype "passive"))
      (node (ref "C77") (pin "1") (pinfunction "1_1") (pintype "passive"))
      (node (ref "C78") (pin "1") (pinfunction "1_1") (pintype "passive"))
      (node (ref "C79") (pin "1") (pinfunction "1_1") (pintype "passive"))
      (node (ref "C8") (pin "1") (pinfunction "1_1") (pintype "passive"))
      (node (ref "C80") (pin "1") (pinfunction "1_1") (pintype "passive"))
      (node (ref "C81") (pin "1") (pinfunction "1_1") (pintype "passive"))
      (node (ref "C82") (pin "1") (pinfunction "1_1") (pintype "passive"))
      (node (ref "C83") (pin "1") (pinfunction "1_1") (pintype "passive"))
      (node (ref "C84") (pin "1") (pinfunction "1_1") (pintype "passive"))
      (node (ref "C85") (pin "1") (pinfunction "1_1") (pintype "passive"))
      (node (ref "C86") (pin "1") (pinfunction "1_1") (pintype "passive"))
      (node (ref "C87") (pin "1") (pinfunction "1_1") (pintype "passive"))
      (node (ref "C88") (pin "1") (pinfunction "1_1") (pintype "passive"))
      (node (ref "C89") (pin "1") (pinfunction "1_1") (pintype "passive"))
      (node (ref "C9") (pin "1") (pinfunction "1_1") (pintype "passive"))
      (node (ref "C90") (pin "1") (pinfunction "1_1") (pintype "passive"))
      (node (ref "C91") (pin "1") (pinfunction "1_1") (pintype "passive"))
      (node (ref "C92") (pin "1") (pinfunction "1_1") (pintype "passive"))
      (node (ref "C93") (pin "1") (pinfunction "1_1") (pintype "passive"))
      (node (ref "C94") (pin "1") (pinfunction "1_1") (pintype "passive"))
      (node (ref "C95") (pin "1") (pinfunction "1_1") (pintype "passive"))
      (node (ref "C96") (pin "1") (pinfunction "1_1") (pintype "passive"))
      (node (ref "C97") (pin "1") (pinfunction "1_1") (pintype "passive"))
      (node (ref "C98") (pin "1") (pinfunction "1_1") (pintype "passive"))
      (node (ref "C99") (pin "1") (pinfunction "1_1") (pintype "passive"))
      (node (ref "IN") (pin "2") (pinfunction "2_2") (pintype "passive"))
      (node (ref "LED1") (pin "LEDVDD") (pinfunction "LEDVDD_LEDVDD") (pintype "power_in"))
      (node (ref "LED1") (pin "VDD") (pinfunction "VDD_VDD") (pintype "power_in"))
      (node (ref "LED10") (pin "LEDVDD") (pinfunction "LEDVDD_LEDVDD") (pintype "power_in"))
      (node (ref "LED10") (pin "VDD") (pinfunction "VDD_VDD") (pintype "power_in"))
      (node (ref "LED100") (pin "LEDVDD") (pinfunction "LEDVDD_LEDVDD") (pintype "power_in"))
      (node (ref "LED100") (pin "VDD") (pinfunction "VDD_VDD") (pintype "power_in"))
      (node (ref "LED11") (pin "LEDVDD") (pinfunction "LEDVDD_LEDVDD") (pintype "power_in"))
      (node (ref "LED11") (pin "VDD") (pinfunction "VDD_VDD") (pintype "power_in"))
      (node (ref "LED12") (pin "LEDVDD") (pinfunction "LEDVDD_LEDVDD") (pintype "power_in"))
      (node (ref "LED12") (pin "VDD") (pinfunction "VDD_VDD") (pintype "power_in"))
      (node (ref "LED13") (pin "LEDVDD") (pinfunction "LEDVDD_LEDVDD") (pintype "power_in"))
      (node (ref "LED13") (pin "VDD") (pinfunction "VDD_VDD") (pintype "power_in"))
      (node (ref "LED14") (pin "LEDVDD") (pinfunction "LEDVDD_LEDVDD") (pintype "power_in"))
      (node (ref "LED14") (pin "VDD") (pinfunction "VDD_VDD") (pintype "power_in"))
      (node (ref "LED15") (pin "LEDVDD") (pinfunction "LEDVDD_LEDVDD") (pintype "power_in"))
      (node (ref "LED15") (pin "VDD") (pinfunction "VDD_VDD") (pintype "power_in"))
      (node (ref "LED16") (pin "LEDVDD") (pinfunction "LEDVDD_LEDVDD") (pintype "power_in"))
      (node (ref "LED16") (pin "VDD") (pinfunction "VDD_VDD") (pintype "power_in"))
      (node (ref "LED17") (pin "LEDVDD") (pinfunction "LEDVDD_LEDVDD") (pintype "power_in"))
      (node (ref "LED17") (pin "VDD") (pinfunction "VDD_VDD") (pintype "power_in"))
      (node (ref "LED18") (pin "LEDVDD") (pinfunction "LEDVDD_LEDVDD") (pintype "power_in"))
      (node (ref "LED18") (pin "VDD") (pinfunction "VDD_VDD") (pintype "power_in"))
      (node (ref "LED19") (pin "LEDVDD") (pinfunction "LEDVDD_LEDVDD") (pintype "power_in"))
      (node (ref "LED19") (pin "VDD") (pinfunction "VDD_VDD") (pintype "power_in"))
      (node (ref "LED2") (pin "LEDVDD") (pinfunction "LEDVDD_LEDVDD") (pintype "power_in"))
      (node (ref "LED2") (pin "VDD") (pinfunction "VDD_VDD") (pintype "power_in"))
      (node (ref "LED20") (pin "LEDVDD") (pinfunction "LEDVDD_LEDVDD") (pintype "power_in"))
      (node (ref "LED20") (pin "VDD") (pinfunction "VDD_VDD") (pintype "power_in"))
      (node (ref "LED21") (pin "LEDVDD") (pinfunction "LEDVDD_LEDVDD") (pintype "power_in"))
      (node (ref "LED21") (pin "VDD") (pinfunction "VDD_VDD") (pintype "power_in"))
      (node (ref "LED22") (pin "LEDVDD") (pinfunction "LEDVDD_LEDVDD") (pintype "power_in"))
      (node (ref "LED22") (pin "VDD") (pinfunction "VDD_VDD") (pintype "power_in"))
      (node (ref "LED23") (pin "LEDVDD") (pinfunction "LEDVDD_LEDVDD") (pintype "power_in"))
      (node (ref "LED23") (pin "VDD") (pinfunction "VDD_VDD") (pintype "power_in"))
      (node (ref "LED24") (pin "LEDVDD") (pinfunction "LEDVDD_LEDVDD") (pintype "power_in"))
      (node (ref "LED24") (pin "VDD") (pinfunction "VDD_VDD") (pintype "power_in"))
      (node (ref "LED25") (pin "LEDVDD") (pinfunction "LEDVDD_LEDVDD") (pintype "power_in"))
      (node (ref "LED25") (pin "VDD") (pinfunction "VDD_VDD") (pintype "power_in"))
      (node (ref "LED26") (pin "LEDVDD") (pinfunction "LEDVDD_LEDVDD") (pintype "power_in"))
      (node (ref "LED26") (pin "VDD") (pinfunction "VDD_VDD") (pintype "power_in"))
      (node (ref "LED27") (pin "LEDVDD") (pinfunction "LEDVDD_LEDVDD") (pintype "power_in"))
      (node (ref "LED27") (pin "VDD") (pinfunction "VDD_VDD") (pintype "power_in"))
      (node (ref "LED28") (pin "LEDVDD") (pinfunction "LEDVDD_LEDVDD") (pintype "power_in"))
      (node (ref "LED28") (pin "VDD") (pinfunction "VDD_VDD") (pintype "power_in"))
      (node (ref "LED29") (pin "LEDVDD") (pinfunction "LEDVDD_LEDVDD") (pintype "power_in"))
      (node (ref "LED29") (pin "VDD") (pinfunction "VDD_VDD") (pintype "power_in"))
      (node (ref "LED3") (pin "LEDVDD") (pinfunction "LEDVDD_LEDVDD") (pintype "power_in"))
      (node (ref "LED3") (pin "VDD") (pinfunction "VDD_VDD") (pintype "power_in"))
      (node (ref "LED30") (pin "LEDVDD") (pinfunction "LEDVDD_LEDVDD") (pintype "power_in"))
      (node (ref "LED30") (pin "VDD") (pinfunction "VDD_VDD") (pintype "power_in"))
      (node (ref "LED31") (pin "LEDVDD") (pinfunction "LEDVDD_LEDVDD") (pintype "power_in"))
      (node (ref "LED31") (pin "VDD") (pinfunction "VDD_VDD") (pintype "power_in"))
      (node (ref "LED32") (pin "LEDVDD") (pinfunction "LEDVDD_LEDVDD") (pintype "power_in"))
      (node (ref "LED32") (pin "VDD") (pinfunction "VDD_VDD") (pintype "power_in"))
      (node (ref "LED33") (pin "LEDVDD") (pinfunction "LEDVDD_LEDVDD") (pintype "power_in"))
      (node (ref "LED33") (pin "VDD") (pinfunction "VDD_VDD") (pintype "power_in"))
      (node (ref "LED34") (pin "LEDVDD") (pinfunction "LEDVDD_LEDVDD") (pintype "power_in"))
      (node (ref "LED34") (pin "VDD") (pinfunction "VDD_VDD") (pintype "power_in"))
      (node (ref "LED35") (pin "LEDVDD") (pinfunction "LEDVDD_LEDVDD") (pintype "power_in"))
      (node (ref "LED35") (pin "VDD") (pinfunction "VDD_VDD") (pintype "power_in"))
      (node (ref "LED36") (pin "LEDVDD") (pinfunction "LEDVDD_LEDVDD") (pintype "power_in"))
      (node (ref "LED36") (pin "VDD") (pinfunction "VDD_VDD") (pintype "power_in"))
      (node (ref "LED37") (pin "LEDVDD") (pinfunction "LEDVDD_LEDVDD") (pintype "power_in"))
      (node (ref "LED37") (pin "VDD") (pinfunction "VDD_VDD") (pintype "power_in"))
      (node (ref "LED38") (pin "LEDVDD") (pinfunction "LEDVDD_LEDVDD") (pintype "power_in"))
      (node (ref "LED38") (pin "VDD") (pinfunction "VDD_VDD") (pintype "power_in"))
      (node (ref "LED39") (pin "LEDVDD") (pinfunction "LEDVDD_LEDVDD") (pintype "power_in"))
      (node (ref "LED39") (pin "VDD") (pinfunction "VDD_VDD") (pintype "power_in"))
      (node (ref "LED4") (pin "LEDVDD") (pinfunction "LEDVDD_LEDVDD") (pintype "power_in"))
      (node (ref "LED4") (pin "VDD") (pinfunction "VDD_VDD") (pintype "power_in"))
      (node (ref "LED40") (pin "LEDVDD") (pinfunction "LEDVDD_LEDVDD") (pintype "power_in"))
      (node (ref "LED40") (pin "VDD") (pinfunction "VDD_VDD") (pintype "power_in"))
      (node (ref "LED41") (pin "LEDVDD") (pinfunction "LEDVDD_LEDVDD") (pintype "power_in"))
      (node (ref "LED41") (pin "VDD") (pinfunction "VDD_VDD") (pintype "power_in"))
      (node (ref "LED42") (pin "LEDVDD") (pinfunction "LEDVDD_LEDVDD") (pintype "power_in"))
      (node (ref "LED42") (pin "VDD") (pinfunction "VDD_VDD") (pintype "power_in"))
      (node (ref "LED43") (pin "LEDVDD") (pinfunction "LEDVDD_LEDVDD") (pintype "power_in"))
      (node (ref "LED43") (pin "VDD") (pinfunction "VDD_VDD") (pintype "power_in"))
      (node (ref "LED44") (pin "LEDVDD") (pinfunction "LEDVDD_LEDVDD") (pintype "power_in"))
      (node (ref "LED44") (pin "VDD") (pinfunction "VDD_VDD") (pintype "power_in"))
      (node (ref "LED45") (pin "LEDVDD") (pinfunction "LEDVDD_LEDVDD") (pintype "power_in"))
      (node (ref "LED45") (pin "VDD") (pinfunction "VDD_VDD") (pintype "power_in"))
      (node (ref "LED46") (pin "LEDVDD") (pinfunction "LEDVDD_LEDVDD") (pintype "power_in"))
      (node (ref "LED46") (pin "VDD") (pinfunction "VDD_VDD") (pintype "power_in"))
      (node (ref "LED47") (pin "LEDVDD") (pinfunction "LEDVDD_LEDVDD") (pintype "power_in"))
      (node (ref "LED47") (pin "VDD") (pinfunction "VDD_VDD") (pintype "power_in"))
      (node (ref "LED48") (pin "LEDVDD") (pinfunction "LEDVDD_LEDVDD") (pintype "power_in"))
      (node (ref "LED48") (pin "VDD") (pinfunction "VDD_VDD") (pintype "power_in"))
      (node (ref "LED49") (pin "LEDVDD") (pinfunction "LEDVDD_LEDVDD") (pintype "power_in"))
      (node (ref "LED49") (pin "VDD") (pinfunction "VDD_VDD") (pintype "power_in"))
      (node (ref "LED5") (pin "LEDVDD") (pinfunction "LEDVDD_LEDVDD") (pintype "power_in"))
      (node (ref "LED5") (pin "VDD") (pinfunction "VDD_VDD") (pintype "power_in"))
      (node (ref "LED50") (pin "LEDVDD") (pinfunction "LEDVDD_LEDVDD") (pintype "power_in"))
      (node (ref "LED50") (pin "VDD") (pinfunction "VDD_VDD") (pintype "power_in"))
      (node (ref "LED51") (pin "LEDVDD") (pinfunction "LEDVDD_LEDVDD") (pintype "power_in"))
      (node (ref "LED51") (pin "VDD") (pinfunction "VDD_VDD") (pintype "power_in"))
      (node (ref "LED52") (pin "LEDVDD") (pinfunction "LEDVDD_LEDVDD") (pintype "power_in"))
      (node (ref "LED52") (pin "VDD") (pinfunction "VDD_VDD") (pintype "power_in"))
      (node (ref "LED53") (pin "LEDVDD") (pinfunction "LEDVDD_LEDVDD") (pintype "power_in"))
      (node (ref "LED53") (pin "VDD") (pinfunction "VDD_VDD") (pintype "power_in"))
      (node (ref "LED54") (pin "LEDVDD") (pinfunction "LEDVDD_LEDVDD") (pintype "power_in"))
      (node (ref "LED54") (pin "VDD") (pinfunction "VDD_VDD") (pintype "power_in"))
      (node (ref "LED55") (pin "LEDVDD") (pinfunction "LEDVDD_LEDVDD") (pintype "power_in"))
      (node (ref "LED55") (pin "VDD") (pinfunction "VDD_VDD") (pintype "power_in"))
      (node (ref "LED56") (pin "LEDVDD") (pinfunction "LEDVDD_LEDVDD") (pintype "power_in"))
      (node (ref "LED56") (pin "VDD") (pinfunction "VDD_VDD") (pintype "power_in"))
      (node (ref "LED57") (pin "LEDVDD") (pinfunction "LEDVDD_LEDVDD") (pintype "power_in"))
      (node (ref "LED57") (pin "VDD") (pinfunction "VDD_VDD") (pintype "power_in"))
      (node (ref "LED58") (pin "LEDVDD") (pinfunction "LEDVDD_LEDVDD") (pintype "power_in"))
      (node (ref "LED58") (pin "VDD") (pinfunction "VDD_VDD") (pintype "power_in"))
      (node (ref "LED59") (pin "LEDVDD") (pinfunction "LEDVDD_LEDVDD") (pintype "power_in"))
      (node (ref "LED59") (pin "VDD") (pinfunction "VDD_VDD") (pintype "power_in"))
      (node (ref "LED6") (pin "LEDVDD") (pinfunction "LEDVDD_LEDVDD") (pintype "power_in"))
      (node (ref "LED6") (pin "VDD") (pinfunction "VDD_VDD") (pintype "power_in"))
      (node (ref "LED60") (pin "LEDVDD") (pinfunction "LEDVDD_LEDVDD") (pintype "power_in"))
      (node (ref "LED60") (pin "VDD") (pinfunction "VDD_VDD") (pintype "power_in"))
      (node (ref "LED61") (pin "LEDVDD") (pinfunction "LEDVDD_LEDVDD") (pintype "power_in"))
      (node (ref "LED61") (pin "VDD") (pinfunction "VDD_VDD") (pintype "power_in"))
      (node (ref "LED62") (pin "LEDVDD") (pinfunction "LEDVDD_LEDVDD") (pintype "power_in"))
      (node (ref "LED62") (pin "VDD") (pinfunction "VDD_VDD") (pintype "power_in"))
      (node (ref "LED63") (pin "LEDVDD") (pinfunction "LEDVDD_LEDVDD") (pintype "power_in"))
      (node (ref "LED63") (pin "VDD") (pinfunction "VDD_VDD") (pintype "power_in"))
      (node (ref "LED64") (pin "LEDVDD") (pinfunction "LEDVDD_LEDVDD") (pintype "power_in"))
      (node (ref "LED64") (pin "VDD") (pinfunction "VDD_VDD") (pintype "power_in"))
      (node (ref "LED65") (pin "LEDVDD") (pinfunction "LEDVDD_LEDVDD") (pintype "power_in"))
      (node (ref "LED65") (pin "VDD") (pinfunction "VDD_VDD") (pintype "power_in"))
      (node (ref "LED66") (pin "LEDVDD") (pinfunction "LEDVDD_LEDVDD") (pintype "power_in"))
      (node (ref "LED66") (pin "VDD") (pinfunction "VDD_VDD") (pintype "power_in"))
      (node (ref "LED67") (pin "LEDVDD") (pinfunction "LEDVDD_LEDVDD") (pintype "power_in"))
      (node (ref "LED67") (pin "VDD") (pinfunction "VDD_VDD") (pintype "power_in"))
      (node (ref "LED68") (pin "LEDVDD") (pinfunction "LEDVDD_LEDVDD") (pintype "power_in"))
      (node (ref "LED68") (pin "VDD") (pinfunction "VDD_VDD") (pintype "power_in"))
      (node (ref "LED69") (pin "LEDVDD") (pinfunction "LEDVDD_LEDVDD") (pintype "power_in"))
      (node (ref "LED69") (pin "VDD") (pinfunction "VDD_VDD") (pintype "power_in"))
      (node (ref "LED7") (pin "LEDVDD") (pinfunction "LEDVDD_LEDVDD") (pintype "power_in"))
      (node (ref "LED7") (pin "VDD") (pinfunction "VDD_VDD") (pintype "power_in"))
      (node (ref "LED70") (pin "LEDVDD") (pinfunction "LEDVDD_LEDVDD") (pintype "power_in"))
      (node (ref "LED70") (pin "VDD") (pinfunction "VDD_VDD") (pintype "power_in"))
      (node (ref "LED71") (pin "LEDVDD") (pinfunction "LEDVDD_LEDVDD") (pintype "power_in"))
      (node (ref "LED71") (pin "VDD") (pinfunction "VDD_VDD") (pintype "power_in"))
      (node (ref "LED72") (pin "LEDVDD") (pinfunction "LEDVDD_LEDVDD") (pintype "power_in"))
      (node (ref "LED72") (pin "VDD") (pinfunction "VDD_VDD") (pintype "power_in"))
      (node (ref "LED73") (pin "LEDVDD") (pinfunction "LEDVDD_LEDVDD") (pintype "power_in"))
      (node (ref "LED73") (pin "VDD") (pinfunction "VDD_VDD") (pintype "power_in"))
      (node (ref "LED74") (pin "LEDVDD") (pinfunction "LEDVDD_LEDVDD") (pintype "power_in"))
      (node (ref "LED74") (pin "VDD") (pinfunction "VDD_VDD") (pintype "power_in"))
      (node (ref "LED75") (pin "LEDVDD") (pinfunction "LEDVDD_LEDVDD") (pintype "power_in"))
      (node (ref "LED75") (pin "VDD") (pinfunction "VDD_VDD") (pintype "power_in"))
      (node (ref "LED76") (pin "LEDVDD") (pinfunction "LEDVDD_LEDVDD") (pintype "power_in"))
      (node (ref "LED76") (pin "VDD") (pinfunction "VDD_VDD") (pintype "power_in"))
      (node (ref "LED77") (pin "LEDVDD") (pinfunction "LEDVDD_LEDVDD") (pintype "power_in"))
      (node (ref "LED77") (pin "VDD") (pinfunction "VDD_VDD") (pintype "power_in"))
      (node (ref "LED78") (pin "LEDVDD") (pinfunction "LEDVDD_LEDVDD") (pintype "power_in"))
      (node (ref "LED78") (pin "VDD") (pinfunction "VDD_VDD") (pintype "power_in"))
      (node (ref "LED79") (pin "LEDVDD") (pinfunction "LEDVDD_LEDVDD") (pintype "power_in"))
      (node (ref "LED79") (pin "VDD") (pinfunction "VDD_VDD") (pintype "power_in"))
      (node (ref "LED8") (pin "LEDVDD") (pinfunction "LEDVDD_LEDVDD") (pintype "power_in"))
      (node (ref "LED8") (pin "VDD") (pinfunction "VDD_VDD") (pintype "power_in"))
      (node (ref "LED80") (pin "LEDVDD") (pinfunction "LEDVDD_LEDVDD") (pintype "power_in"))
      (node (ref "LED80") (pin "VDD") (pinfunction "VDD_VDD") (pintype "power_in"))
      (node (ref "LED81") (pin "LEDVDD") (pinfunction "LEDVDD_LEDVDD") (pintype "power_in"))
      (node (ref "LED81") (pin "VDD") (pinfunction "VDD_VDD") (pintype "power_in"))
      (node (ref "LED82") (pin "LEDVDD") (pinfunction "LEDVDD_LEDVDD") (pintype "power_in"))
      (node (ref "LED82") (pin "VDD") (pinfunction "VDD_VDD") (pintype "power_in"))
      (node (ref "LED83") (pin "LEDVDD") (pinfunction "LEDVDD_LEDVDD") (pintype "power_in"))
      (node (ref "LED83") (pin "VDD") (pinfunction "VDD_VDD") (pintype "power_in"))
      (node (ref "LED84") (pin "LEDVDD") (pinfunction "LEDVDD_LEDVDD") (pintype "power_in"))
      (node (ref "LED84") (pin "VDD") (pinfunction "VDD_VDD") (pintype "power_in"))
      (node (ref "LED85") (pin "LEDVDD") (pinfunction "LEDVDD_LEDVDD") (pintype "power_in"))
      (node (ref "LED85") (pin "VDD") (pinfunction "VDD_VDD") (pintype "power_in"))
      (node (ref "LED86") (pin "LEDVDD") (pinfunction "LEDVDD_LEDVDD") (pintype "power_in"))
      (node (ref "LED86") (pin "VDD") (pinfunction "VDD_VDD") (pintype "power_in"))
      (node (ref "LED87") (pin "LEDVDD") (pinfunction "LEDVDD_LEDVDD") (pintype "power_in"))
      (node (ref "LED87") (pin "VDD") (pinfunction "VDD_VDD") (pintype "power_in"))
      (node (ref "LED88") (pin "LEDVDD") (pinfunction "LEDVDD_LEDVDD") (pintype "power_in"))
      (node (ref "LED88") (pin "VDD") (pinfunction "VDD_VDD") (pintype "power_in"))
      (node (ref "LED89") (pin "LEDVDD") (pinfunction "LEDVDD_LEDVDD") (pintype "power_in"))
      (node (ref "LED89") (pin "VDD") (pinfunction "VDD_VDD") (pintype "power_in"))
      (node (ref "LED9") (pin "LEDVDD") (pinfunction "LEDVDD_LEDVDD") (pintype "power_in"))
      (node (ref "LED9") (pin "VDD") (pinfunction "VDD_VDD") (pintype "power_in"))
      (node (ref "LED90") (pin "LEDVDD") (pinfunction "LEDVDD_LEDVDD") (pintype "power_in"))
      (node (ref "LED90") (pin "VDD") (pinfunction "VDD_VDD") (pintype "power_in"))
      (node (ref "LED91") (pin "LEDVDD") (pinfunction "LEDVDD_LEDVDD") (pintype "power_in"))
      (node (ref "LED91") (pin "VDD") (pinfunction "VDD_VDD") (pintype "power_in"))
      (node (ref "LED92") (pin "LEDVDD") (pinfunction "LEDVDD_LEDVDD") (pintype "power_in"))
      (node (ref "LED92") (pin "VDD") (pinfunction "VDD_VDD") (pintype "power_in"))
      (node (ref "LED93") (pin "LEDVDD") (pinfunction "LEDVDD_LEDVDD") (pintype "power_in"))
      (node (ref "LED93") (pin "VDD") (pinfunction "VDD_VDD") (pintype "power_in"))
      (node (ref "LED94") (pin "LEDVDD") (pinfunction "LEDVDD_LEDVDD") (pintype "power_in"))
      (node (ref "LED94") (pin "VDD") (pinfunction "VDD_VDD") (pintype "power_in"))
      (node (ref "LED95") (pin "LEDVDD") (pinfunction "LEDVDD_LEDVDD") (pintype "power_in"))
      (node (ref "LED95") (pin "VDD") (pinfunction "VDD_VDD") (pintype "power_in"))
      (node (ref "LED96") (pin "LEDVDD") (pinfunction "LEDVDD_LEDVDD") (pintype "power_in"))
      (node (ref "LED96") (pin "VDD") (pinfunction "VDD_VDD") (pintype "power_in"))
      (node (ref "LED97") (pin "LEDVDD") (pinfunction "LEDVDD_LEDVDD") (pintype "power_in"))
      (node (ref "LED97") (pin "VDD") (pinfunction "VDD_VDD") (pintype "power_in"))
      (node (ref "LED98") (pin "LEDVDD") (pinfunction "LEDVDD_LEDVDD") (pintype "power_in"))
      (node (ref "LED98") (pin "VDD") (pinfunction "VDD_VDD") (pintype "power_in"))
      (node (ref "LED99") (pin "LEDVDD") (pinfunction "LEDVDD_LEDVDD") (pintype "power_in"))
      (node (ref "LED99") (pin "VDD") (pinfunction "VDD_VDD") (pintype "power_in"))
    )
    (net (code "2") (name "DIN") (class "Default")
      (node (ref "IN") (pin "3") (pinfunction "3_3") (pintype "passive"))
      (node (ref "LED1") (pin "DI") (pinfunction "DI_DI") (pintype "input"))
    )
    (net (code "3") (name "GND") (class "Default")
      (node (ref "C1") (pin "2") (pinfunction "2_2") (pintype "passive"))
      (node (ref "C10") (pin "2") (pinfunction "2_2") (pintype "passive"))
      (node (ref "C100") (pin "2") (pinfunction "2_2") (pintype "passive"))
      (node (ref "C11") (pin "2") (pinfunction "2_2") (pintype "passive"))
      (node (ref "C12") (pin "2") (pinfunction "2_2") (pintype "passive"))
      (node (ref "C13") (pin "2") (pinfunction "2_2") (pintype "passive"))
      (node (ref "C14") (pin "2") (pinfunction "2_2") (pintype "passive"))
      (node (ref "C15") (pin "2") (pinfunction "2_2") (pintype "passive"))
      (node (ref "C16") (pin "2") (pinfunction "2_2") (pintype "passive"))
      (node (ref "C17") (pin "2") (pinfunction "2_2") (pintype "passive"))
      (node (ref "C18") (pin "2") (pinfunction "2_2") (pintype "passive"))
      (node (ref "C19") (pin "2") (pinfunction "2_2") (pintype "passive"))
      (node (ref "C2") (pin "2") (pinfunction "2_2") (pintype "passive"))
      (node (ref "C20") (pin "2") (pinfunction "2_2") (pintype "passive"))
      (node (ref "C21") (pin "2") (pinfunction "2_2") (pintype "passive"))
      (node (ref "C22") (pin "2") (pinfunction "2_2") (pintype "passive"))
      (node (ref "C23") (pin "2") (pinfunction "2_2") (pintype "passive"))
      (node (ref "C24") (pin "2") (pinfunction "2_2") (pintype "passive"))
      (node (ref "C25") (pin "2") (pinfunction "2_2") (pintype "passive"))
      (node (ref "C26") (pin "2") (pinfunction "2_2") (pintype "passive"))
      (node (ref "C27") (pin "2") (pinfunction "2_2") (pintype "passive"))
      (node (ref "C28") (pin "2") (pinfunction "2_2") (pintype "passive"))
      (node (ref "C29") (pin "2") (pinfunction "2_2") (pintype "passive"))
      (node (ref "C3") (pin "2") (pinfunction "2_2") (pintype "passive"))
      (node (ref "C30") (pin "2") (pinfunction "2_2") (pintype "passive"))
      (node (ref "C31") (pin "2") (pinfunction "2_2") (pintype "passive"))
      (node (ref "C32") (pin "2") (pinfunction "2_2") (pintype "passive"))
      (node (ref "C33") (pin "2") (pinfunction "2_2") (pintype "passive"))
      (node (ref "C34") (pin "2") (pinfunction "2_2") (pintype "passive"))
      (node (ref "C35") (pin "2") (pinfunction "2_2") (pintype "passive"))
      (node (ref "C36") (pin "2") (pinfunction "2_2") (pintype "passive"))
      (node (ref "C37") (pin "2") (pinfunction "2_2") (pintype "passive"))
      (node (ref "C38") (pin "2") (pinfunction "2_2") (pintype "passive"))
      (node (ref "C39") (pin "2") (pinfunction "2_2") (pintype "passive"))
      (node (ref "C4") (pin "2") (pinfunction "2_2") (pintype "passive"))
      (node (ref "C40") (pin "2") (pinfunction "2_2") (pintype "passive"))
      (node (ref "C41") (pin "2") (pinfunction "2_2") (pintype "passive"))
      (node (ref "C42") (pin "2") (pinfunction "2_2") (pintype "passive"))
      (node (ref "C43") (pin "2") (pinfunction "2_2") (pintype "passive"))
      (node (ref "C44") (pin "2") (pinfunction "2_2") (pintype "passive"))
      (node (ref "C45") (pin "2") (pinfunction "2_2") (pintype "passive"))
      (node (ref "C46") (pin "2") (pinfunction "2_2") (pintype "passive"))
      (node (ref "C47") (pin "2") (pinfunction "2_2") (pintype "passive"))
      (node (ref "C48") (pin "2") (pinfunction "2_2") (pintype "passive"))
      (node (ref "C49") (pin "2") (pinfunction "2_2") (pintype "passive"))
      (node (ref "C5") (pin "2") (pinfunction "2_2") (pintype "passive"))
      (node (ref "C50") (pin "2") (pinfunction "2_2") (pintype "passive"))
      (node (ref "C51") (pin "2") (pinfunction "2_2") (pintype "passive"))
      (node (ref "C52") (pin "2") (pinfunction "2_2") (pintype "passive"))
      (node (ref "C53") (pin "2") (pinfunction "2_2") (pintype "passive"))
      (node (ref "C54") (pin "2") (pinfunction "2_2") (pintype "passive"))
      (node (ref "C55") (pin "2") (pinfunction "2_2") (pintype "passive"))
      (node (ref "C56") (pin "2") (pinfunction "2_2") (pintype "passive"))
      (node (ref "C57") (pin "2") (pinfunction "2_2") (pintype "passive"))
      (node (ref "C58") (pin "2") (pinfunction "2_2") (pintype "passive"))
      (node (ref "C59") (pin "2") (pinfunction "2_2") (pintype "passive"))
      (node (ref "C6") (pin "2") (pinfunction "2_2") (pintype "passive"))
      (node (ref "C60") (pin "2") (pinfunction "2_2") (pintype "passive"))
      (node (ref "C61") (pin "2") (pinfunction "2_2") (pintype "passive"))
      (node (ref "C62") (pin "2") (pinfunction "2_2") (pintype "passive"))
      (node (ref "C63") (pin "2") (pinfunction "2_2") (pintype "passive"))
      (node (ref "C64") (pin "2") (pinfunction "2_2") (pintype "passive"))
      (node (ref "C65") (pin "2") (pinfunction "2_2") (pintype "passive"))
      (node (ref "C66") (pin "2") (pinfunction "2_2") (pintype "passive"))
      (node (ref "C67") (pin "2") (pinfunction "2_2") (pintype "passive"))
      (node (ref "C68") (pin "2") (pinfunction "2_2") (pintype "passive"))
      (node (ref "C69") (pin "2") (pinfunction "2_2") (pintype "passive"))
      (node (ref "C7") (pin "2") (pinfunction "2_2") (pintype "passive"))
      (node (ref "C70") (pin "2") (pinfunction "2_2") (pintype "passive"))
      (node (ref "C71") (pin "2") (pinfunction "2_2") (pintype "passive"))
      (node (ref "C72") (pin "2") (pinfunction "2_2") (pintype "passive"))
      (node (ref "C73") (pin "2") (pinfunction "2_2") (pintype "passive"))
      (node (ref "C74") (pin "2") (pinfunction "2_2") (pintype "passive"))
      (node (ref "C75") (pin "2") (pinfunction "2_2") (pintype "passive"))
      (node (ref "C76") (pin "2") (pinfunction "2_2") (pintype "passive"))
      (node (ref "C77") (pin "2") (pinfunction "2_2") (pintype "passive"))
      (node (ref "C78") (pin "2") (pinfunction "2_2") (pintype "passive"))
      (node (ref "C79") (pin "2") (pinfunction "2_2") (pintype "passive"))
      (node (ref "C8") (pin "2") (pinfunction "2_2") (pintype "passive"))
      (node (ref "C80") (pin "2") (pinfunction "2_2") (pintype "passive"))
      (node (ref "C81") (pin "2") (pinfunction "2_2") (pintype "passive"))
      (node (ref "C82") (pin "2") (pinfunction "2_2") (pintype "passive"))
      (node (ref "C83") (pin "2") (pinfunction "2_2") (pintype "passive"))
      (node (ref "C84") (pin "2") (pinfunction "2_2") (pintype "passive"))
      (node (ref "C85") (pin "2") (pinfunction "2_2") (pintype "passive"))
      (node (ref "C86") (pin "2") (pinfunction "2_2") (pintype "passive"))
      (node (ref "C87") (pin "2") (pinfunction "2_2") (pintype "passive"))
      (node (ref "C88") (pin "2") (pinfunction "2_2") (pintype "passive"))
      (node (ref "C89") (pin "2") (pinfunction "2_2") (pintype "passive"))
      (node (ref "C9") (pin "2") (pinfunction "2_2") (pintype "passive"))
      (node (ref "C90") (pin "2") (pinfunction "2_2") (pintype "passive"))
      (node (ref "C91") (pin "2") (pinfunction "2_2") (pintype "passive"))
      (node (ref "C92") (pin "2") (pinfunction "2_2") (pintype "passive"))
      (node (ref "C93") (pin "2") (pinfunction "2_2") (pintype "passive"))
      (node (ref "C94") (pin "2") (pinfunction "2_2") (pintype "passive"))
      (node (ref "C95") (pin "2") (pinfunction "2_2") (pintype "passive"))
      (node (ref "C96") (pin "2") (pinfunction "2_2") (pintype "passive"))
      (node (ref "C97") (pin "2") (pinfunction "2_2") (pintype "passive"))
      (node (ref "C98") (pin "2") (pinfunction "2_2") (pintype "passive"))
      (node (ref "C99") (pin "2") (pinfunction "2_2") (pintype "passive"))
      (node (ref "IN") (pin "1") (pinfunction "1_1") (pintype "passive"))
      (node (ref "LED1") (pin "VSS") (pinfunction "GND_VSS") (pintype "power_in"))
      (node (ref "LED10") (pin "VSS") (pinfunction "GND_VSS") (pintype "power_in"))
      (node (ref "LED100") (pin "VSS") (pinfunction "GND_VSS") (pintype "power_in"))
      (node (ref "LED11") (pin "VSS") (pinfunction "GND_VSS") (pintype "power_in"))
      (node (ref "LED12") (pin "VSS") (pinfunction "GND_VSS") (pintype "power_in"))
      (node (ref "LED13") (pin "VSS") (pinfunction "GND_VSS") (pintype "power_in"))
      (node (ref "LED14") (pin "VSS") (pinfunction "GND_VSS") (pintype "power_in"))
      (node (ref "LED15") (pin "VSS") (pinfunction "GND_VSS") (pintype "power_in"))
      (node (ref "LED16") (pin "VSS") (pinfunction "GND_VSS") (pintype "power_in"))
      (node (ref "LED17") (pin "VSS") (pinfunction "GND_VSS") (pintype "power_in"))
      (node (ref "LED18") (pin "VSS") (pinfunction "GND_VSS") (pintype "power_in"))
      (node (ref "LED19") (pin "VSS") (pinfunction "GND_VSS") (pintype "power_in"))
      (node (ref "LED2") (pin "VSS") (pinfunction "GND_VSS") (pintype "power_in"))
      (node (ref "LED20") (pin "VSS") (pinfunction "GND_VSS") (pintype "power_in"))
      (node (ref "LED21") (pin "VSS") (pinfunction "GND_VSS") (pintype "power_in"))
      (node (ref "LED22") (pin "VSS") (pinfunction "GND_VSS") (pintype "power_in"))
      (node (ref "LED23") (pin "VSS") (pinfunction "GND_VSS") (pintype "power_in"))
      (node (ref "LED24") (pin "VSS") (pinfunction "GND_VSS") (pintype "power_in"))
      (node (ref "LED25") (pin "VSS") (pinfunction "GND_VSS") (pintype "power_in"))
      (node (ref "LED26") (pin "VSS") (pinfunction "GND_VSS") (pintype "power_in"))
      (node (ref "LED27") (pin "VSS") (pinfunction "GND_VSS") (pintype "power_in"))
      (node (ref "LED28") (pin "VSS") (pinfunction "GND_VSS") (pintype "power_in"))
      (node (ref "LED29") (pin "VSS") (pinfunction "GND_VSS") (pintype "power_in"))
      (node (ref "LED3") (pin "VSS") (pinfunction "GND_VSS") (pintype "power_in"))
      (node (ref "LED30") (pin "VSS") (pinfunction "GND_VSS") (pintype "power_in"))
      (node (ref "LED31") (pin "VSS") (pinfunction "GND_VSS") (pintype "power_in"))
      (node (ref "LED32") (pin "VSS") (pinfunction "GND_VSS") (pintype "power_in"))
      (node (ref "LED33") (pin "VSS") (pinfunction "GND_VSS") (pintype "power_in"))
      (node (ref "LED34") (pin "VSS") (pinfunction "GND_VSS") (pintype "power_in"))
      (node (ref "LED35") (pin "VSS") (pinfunction "GND_VSS") (pintype "power_in"))
      (node (ref "LED36") (pin "VSS") (pinfunction "GND_VSS") (pintype "power_in"))
      (node (ref "LED37") (pin "VSS") (pinfunction "GND_VSS") (pintype "power_in"))
      (node (ref "LED38") (pin "VSS") (pinfunction "GND_VSS") (pintype "power_in"))
      (node (ref "LED39") (pin "VSS") (pinfunction "GND_VSS") (pintype "power_in"))
      (node (ref "LED4") (pin "VSS") (pinfunction "GND_VSS") (pintype "power_in"))
      (node (ref "LED40") (pin "VSS") (pinfunction "GND_VSS") (pintype "power_in"))
      (node (ref "LED41") (pin "VSS") (pinfunction "GND_VSS") (pintype "power_in"))
      (node (ref "LED42") (pin "VSS") (pinfunction "GND_VSS") (pintype "power_in"))
      (node (ref "LED43") (pin "VSS") (pinfunction "GND_VSS") (pintype "power_in"))
      (node (ref "LED44") (pin "VSS") (pinfunction "GND_VSS") (pintype "power_in"))
      (node (ref "LED45") (pin "VSS") (pinfunction "GND_VSS") (pintype "power_in"))
      (node (ref "LED46") (pin "VSS") (pinfunction "GND_VSS") (pintype "power_in"))
      (node (ref "LED47") (pin "VSS") (pinfunction "GND_VSS") (pintype "power_in"))
      (node (ref "LED48") (pin "VSS") (pinfunction "GND_VSS") (pintype "power_in"))
      (node (ref "LED49") (pin "VSS") (pinfunction "GND_VSS") (pintype "power_in"))
      (node (ref "LED5") (pin "VSS") (pinfunction "GND_VSS") (pintype "power_in"))
      (node (ref "LED50") (pin "VSS") (pinfunction "GND_VSS") (pintype "power_in"))
      (node (ref "LED51") (pin "VSS") (pinfunction "GND_VSS") (pintype "power_in"))
      (node (ref "LED52") (pin "VSS") (pinfunction "GND_VSS") (pintype "power_in"))
      (node (ref "LED53") (pin "VSS") (pinfunction "GND_VSS") (pintype "power_in"))
      (node (ref "LED54") (pin "VSS") (pinfunction "GND_VSS") (pintype "power_in"))
      (node (ref "LED55") (pin "VSS") (pinfunction "GND_VSS") (pintype "power_in"))
      (node (ref "LED56") (pin "VSS") (pinfunction "GND_VSS") (pintype "power_in"))
      (node (ref "LED57") (pin "VSS") (pinfunction "GND_VSS") (pintype "power_in"))
      (node (ref "LED58") (pin "VSS") (pinfunction "GND_VSS") (pintype "power_in"))
      (node (ref "LED59") (pin "VSS") (pinfunction "GND_VSS") (pintype "power_in"))
      (node (ref "LED6") (pin "VSS") (pinfunction "GND_VSS") (pintype "power_in"))
      (node (ref "LED60") (pin "VSS") (pinfunction "GND_VSS") (pintype "power_in"))
      (node (ref "LED61") (pin "VSS") (pinfunction "GND_VSS") (pintype "power_in"))
      (node (ref "LED62") (pin "VSS") (pinfunction "GND_VSS") (pintype "power_in"))
      (node (ref "LED63") (pin "VSS") (pinfunction "GND_VSS") (pintype "power_in"))
      (node (ref "LED64") (pin "VSS") (pinfunction "GND_VSS") (pintype "power_in"))
      (node (ref "LED65") (pin "VSS") (pinfunction "GND_VSS") (pintype "power_in"))
      (node (ref "LED66") (pin "VSS") (pinfunction "GND_VSS") (pintype "power_in"))
      (node (ref "LED67") (pin "VSS") (pinfunction "GND_VSS") (pintype "power_in"))
      (node (ref "LED68") (pin "VSS") (pinfunction "GND_VSS") (pintype "power_in"))
      (node (ref "LED69") (pin "VSS") (pinfunction "GND_VSS") (pintype "power_in"))
      (node (ref "LED7") (pin "VSS") (pinfunction "GND_VSS") (pintype "power_in"))
      (node (ref "LED70") (pin "VSS") (pinfunction "GND_VSS") (pintype "power_in"))
      (node (ref "LED71") (pin "VSS") (pinfunction "GND_VSS") (pintype "power_in"))
      (node (ref "LED72") (pin "VSS") (pinfunction "GND_VSS") (pintype "power_in"))
      (node (ref "LED73") (pin "VSS") (pinfunction "GND_VSS") (pintype "power_in"))
      (node (ref "LED74") (pin "VSS") (pinfunction "GND_VSS") (pintype "power_in"))
      (node (ref "LED75") (pin "VSS") (pinfunction "GND_VSS") (pintype "power_in"))
      (node (ref "LED76") (pin "VSS") (pinfunction "GND_VSS") (pintype "power_in"))
      (node (ref "LED77") (pin "VSS") (pinfunction "GND_VSS") (pintype "power_in"))
      (node (ref "LED78") (pin "VSS") (pinfunction "GND_VSS") (pintype "power_in"))
      (node (ref "LED79") (pin "VSS") (pinfunction "GND_VSS") (pintype "power_in"))
      (node (ref "LED8") (pin "VSS") (pinfunction "GND_VSS") (pintype "power_in"))
      (node (ref "LED80") (pin "VSS") (pinfunction "GND_VSS") (pintype "power_in"))
      (node (ref "LED81") (pin "VSS") (pinfunction "GND_VSS") (pintype "power_in"))
      (node (ref "LED82") (pin "VSS") (pinfunction "GND_VSS") (pintype "power_in"))
      (node (ref "LED83") (pin "VSS") (pinfunction "GND_VSS") (pintype "power_in"))
      (node (ref "LED84") (pin "VSS") (pinfunction "GND_VSS") (pintype "power_in"))
      (node (ref "LED85") (pin "VSS") (pinfunction "GND_VSS") (pintype "power_in"))
      (node (ref "LED86") (pin "VSS") (pinfunction "GND_VSS") (pintype "power_in"))
      (node (ref "LED87") (pin "VSS") (pinfunction "GND_VSS") (pintype "power_in"))
      (node (ref "LED88") (pin "VSS") (pinfunction "GND_VSS") (pintype "power_in"))
      (node (ref "LED89") (pin "VSS") (pinfunction "GND_VSS") (pintype "power_in"))
      (node (ref "LED9") (pin "VSS") (pinfunction "GND_VSS") (pintype "power_in"))
      (node (ref "LED90") (pin "VSS") (pinfunction "GND_VSS") (pintype "power_in"))
      (node (ref "LED91") (pin "VSS") (pinfunction "GND_VSS") (pintype "power_in"))
      (node (ref "LED92") (pin "VSS") (pinfunction "GND_VSS") (pintype "power_in"))
      (node (ref "LED93") (pin "VSS") (pinfunction "GND_VSS") (pintype "power_in"))
      (node (ref "LED94") (pin "VSS") (pinfunction "GND_VSS") (pintype "power_in"))
      (node (ref "LED95") (pin "VSS") (pinfunction "GND_VSS") (pintype "power_in"))
      (node (ref "LED96") (pin "VSS") (pinfunction "GND_VSS") (pintype "power_in"))
      (node (ref "LED97") (pin "VSS") (pinfunction "GND_VSS") (pintype "power_in"))
      (node (ref "LED98") (pin "VSS") (pinfunction "GND_VSS") (pintype "power_in"))
      (node (ref "LED99") (pin "VSS") (pinfunction "GND_VSS") (pintype "power_in"))
    )
    (net (code "4") (name "Net-(LED1-PadDO)") (class "Default")
      (node (ref "LED1") (pin "DO") (pinfunction "DO_DO") (pintype "output"))
      (node (ref "LED2") (pin "DI") (pinfunction "DI_DI") (pintype "input"))
    )
    (net (code "5") (name "Net-(LED2-PadDO)") (class "Default")
      (node (ref "LED2") (pin "DO") (pinfunction "DO_DO") (pintype "output"))
      (node (ref "LED3") (pin "DI") (pinfunction "DI_DI") (pintype "input"))
    )
    (net (code "6") (name "Net-(LED3-PadDO)") (class "Default")
      (node (ref "LED3") (pin "DO") (pinfunction "DO_DO") (pintype "output"))
      (node (ref "LED4") (pin "DI") (pinfunction "DI_DI") (pintype "input"))
    )
    (net (code "7") (name "Net-(LED4-PadDO)") (class "Default")
      (node (ref "LED4") (pin "DO") (pinfunction "DO_DO") (pintype "output"))
      (node (ref "LED5") (pin "DI") (pinfunction "DI_DI") (pintype "input"))
    )
    (net (code "8") (name "Net-(LED5-PadDO)") (class "Default")
      (node (ref "LED5") (pin "DO") (pinfunction "DO_DO") (pintype "output"))
      (node (ref "LED6") (pin "DI") (pinfunction "DI_DI") (pintype "input"))
    )
    (net (code "9") (name "Net-(LED6-PadDO)") (class "Default")
      (node (ref "LED6") (pin "DO") (pinfunction "DO_DO") (pintype "output"))
      (node (ref "LED7") (pin "DI") (pinfunction "DI_DI") (pintype "input"))
    )
    (net (code "10") (name "Net-(LED7-PadDO)") (class "Default")
      (node (ref "LED7") (pin "DO") (pinfunction "DO_DO") (pintype "output"))
      (node (ref "LED8") (pin "DI") (pinfunction "DI_DI") (pintype "input"))
    )
    (net (code "11") (name "Net-(LED8-PadDO)") (class "Default")
      (node (ref "LED8") (pin "DO") (pinfunction "DO_DO") (pintype "output"))
      (node (ref "LED9") (pin "DI") (pinfunction "DI_DI") (pintype "input"))
    )
    (net (code "12") (name "Net-(LED10-PadDI)") (class "Default")
      (node (ref "LED10") (pin "DI") (pinfunction "DI_DI") (pintype "input"))
      (node (ref "LED9") (pin "DO") (pinfunction "DO_DO") (pintype "output"))
    )
    (net (code "13") (name "Net-(LED10-PadDO)") (class "Default")
      (node (ref "LED10") (pin "DO") (pinfunction "DO_DO") (pintype "output"))
      (node (ref "LED11") (pin "DI") (pinfunction "DI_DI") (pintype "input"))
    )
    (net (code "14") (name "Net-(LED11-PadDO)") (class "Default")
      (node (ref "LED11") (pin "DO") (pinfunction "DO_DO") (pintype "output"))
      (node (ref "LED12") (pin "DI") (pinfunction "DI_DI") (pintype "input"))
    )
    (net (code "15") (name "Net-(LED12-PadDO)") (class "Default")
      (node (ref "LED12") (pin "DO") (pinfunction "DO_DO") (pintype "output"))
      (node (ref "LED13") (pin "DI") (pinfunction "DI_DI") (pintype "input"))
    )
    (net (code "16") (name "Net-(LED13-PadDO)") (class "Default")
      (node (ref "LED13") (pin "DO") (pinfunction "DO_DO") (pintype "output"))
      (node (ref "LED14") (pin "DI") (pinfunction "DI_DI") (pintype "input"))
    )
    (net (code "17") (name "Net-(LED14-PadDO)") (class "Default")
      (node (ref "LED14") (pin "DO") (pinfunction "DO_DO") (pintype "output"))
      (node (ref "LED15") (pin "DI") (pinfunction "DI_DI") (pintype "input"))
    )
    (net (code "18") (name "Net-(LED15-PadDO)") (class "Default")
      (node (ref "LED15") (pin "DO") (pinfunction "DO_DO") (pintype "output"))
      (node (ref "LED16") (pin "DI") (pinfunction "DI_DI") (pintype "input"))
    )
    (net (code "19") (name "Net-(LED16-PadDO)") (class "Default")
      (node (ref "LED16") (pin "DO") (pinfunction "DO_DO") (pintype "output"))
      (node (ref "LED17") (pin "DI") (pinfunction "DI_DI") (pintype "input"))
    )
    (net (code "20") (name "Net-(LED17-PadDO)") (class "Default")
      (node (ref "LED17") (pin "DO") (pinfunction "DO_DO") (pintype "output"))
      (node (ref "LED18") (pin "DI") (pinfunction "DI_DI") (pintype "input"))
    )
    (net (code "21") (name "Net-(LED18-PadDO)") (class "Default")
      (node (ref "LED18") (pin "DO") (pinfunction "DO_DO") (pintype "output"))
      (node (ref "LED19") (pin "DI") (pinfunction "DI_DI") (pintype "input"))
    )
    (net (code "22") (name "Net-(LED19-PadDO)") (class "Default")
      (node (ref "LED19") (pin "DO") (pinfunction "DO_DO") (pintype "output"))
      (node (ref "LED20") (pin "DI") (pinfunction "DI_DI") (pintype "input"))
    )
    (net (code "23") (name "Net-(LED20-PadDO)") (class "Default")
      (node (ref "LED20") (pin "DO") (pinfunction "DO_DO") (pintype "output"))
      (node (ref "LED21") (pin "DI") (pinfunction "DI_DI") (pintype "input"))
    )
    (net (code "24") (name "Net-(LED21-PadDO)") (class "Default")
      (node (ref "LED21") (pin "DO") (pinfunction "DO_DO") (pintype "output"))
      (node (ref "LED22") (pin "DI") (pinfunction "DI_DI") (pintype "input"))
    )
    (net (code "25") (name "Net-(LED22-PadDO)") (class "Default")
      (node (ref "LED22") (pin "DO") (pinfunction "DO_DO") (pintype "output"))
      (node (ref "LED23") (pin "DI") (pinfunction "DI_DI") (pintype "input"))
    )
    (net (code "26") (name "Net-(LED23-PadDO)") (class "Default")
      (node (ref "LED23") (pin "DO") (pinfunction "DO_DO") (pintype "output"))
      (node (ref "LED24") (pin "DI") (pinfunction "DI_DI") (pintype "input"))
    )
    (net (code "27") (name "Net-(LED24-PadDO)") (class "Default")
      (node (ref "LED24") (pin "DO") (pinfunction "DO_DO") (pintype "output"))
      (node (ref "LED25") (pin "DI") (pinfunction "DI_DI") (pintype "input"))
    )
    (net (code "28") (name "Net-(LED25-PadDO)") (class "Default")
      (node (ref "LED25") (pin "DO") (pinfunction "DO_DO") (pintype "output"))
      (node (ref "LED26") (pin "DI") (pinfunction "DI_DI") (pintype "input"))
    )
    (net (code "29") (name "Net-(LED26-PadDO)") (class "Default")
      (node (ref "LED26") (pin "DO") (pinfunction "DO_DO") (pintype "output"))
      (node (ref "LED27") (pin "DI") (pinfunction "DI_DI") (pintype "input"))
    )
    (net (code "30") (name "Net-(LED27-PadDO)") (class "Default")
      (node (ref "LED27") (pin "DO") (pinfunction "DO_DO") (pintype "output"))
      (node (ref "LED28") (pin "DI") (pinfunction "DI_DI") (pintype "input"))
    )
    (net (code "31") (name "Net-(LED28-PadDO)") (class "Default")
      (node (ref "LED28") (pin "DO") (pinfunction "DO_DO") (pintype "output"))
      (node (ref "LED29") (pin "DI") (pinfunction "DI_DI") (pintype "input"))
    )
    (net (code "32") (name "Net-(LED29-PadDO)") (class "Default")
      (node (ref "LED29") (pin "DO") (pinfunction "DO_DO") (pintype "output"))
      (node (ref "LED30") (pin "DI") (pinfunction "DI_DI") (pintype "input"))
    )
    (net (code "33") (name "Net-(LED30-PadDO)") (class "Default")
      (node (ref "LED30") (pin "DO") (pinfunction "DO_DO") (pintype "output"))
      (node (ref "LED31") (pin "DI") (pinfunction "DI_DI") (pintype "input"))
    )
    (net (code "34") (name "Net-(LED31-PadDO)") (class "Default")
      (node (ref "LED31") (pin "DO") (pinfunction "DO_DO") (pintype "output"))
      (node (ref "LED32") (pin "DI") (pinfunction "DI_DI") (pintype "input"))
    )
    (net (code "35") (name "Net-(LED32-PadDO)") (class "Default")
      (node (ref "LED32") (pin "DO") (pinfunction "DO_DO") (pintype "output"))
      (node (ref "LED33") (pin "DI") (pinfunction "DI_DI") (pintype "input"))
    )
    (net (code "36") (name "Net-(LED33-PadDO)") (class "Default")
      (node (ref "LED33") (pin "DO") (pinfunction "DO_DO") (pintype "output"))
      (node (ref "LED34") (pin "DI") (pinfunction "DI_DI") (pintype "input"))
    )
    (net (code "37") (name "Net-(LED34-PadDO)") (class "Default")
      (node (ref "LED34") (pin "DO") (pinfunction "DO_DO") (pintype "output"))
      (node (ref "LED35") (pin "DI") (pinfunction "DI_DI") (pintype "input"))
    )
    (net (code "38") (name "Net-(LED35-PadDO)") (class "Default")
      (node (ref "LED35") (pin "DO") (pinfunction "DO_DO") (pintype "output"))
      (node (ref "LED36") (pin "DI") (pinfunction "DI_DI") (pintype "input"))
    )
    (net (code "39") (name "Net-(LED36-PadDO)") (class "Default")
      (node (ref "LED36") (pin "DO") (pinfunction "DO_DO") (pintype "output"))
      (node (ref "LED37") (pin "DI") (pinfunction "DI_DI") (pintype "input"))
    )
    (net (code "40") (name "Net-(LED37-PadDO)") (class "Default")
      (node (ref "LED37") (pin "DO") (pinfunction "DO_DO") (pintype "output"))
      (node (ref "LED38") (pin "DI") (pinfunction "DI_DI") (pintype "input"))
    )
    (net (code "41") (name "Net-(LED38-PadDO)") (class "Default")
      (node (ref "LED38") (pin "DO") (pinfunction "DO_DO") (pintype "output"))
      (node (ref "LED39") (pin "DI") (pinfunction "DI_DI") (pintype "input"))
    )
    (net (code "42") (name "Net-(LED39-PadDO)") (class "Default")
      (node (ref "LED39") (pin "DO") (pinfunction "DO_DO") (pintype "output"))
      (node (ref "LED40") (pin "DI") (pinfunction "DI_DI") (pintype "input"))
    )
    (net (code "43") (name "Net-(LED40-PadDO)") (class "Default")
      (node (ref "LED40") (pin "DO") (pinfunction "DO_DO") (pintype "output"))
      (node (ref "LED41") (pin "DI") (pinfunction "DI_DI") (pintype "input"))
    )
    (net (code "44") (name "Net-(LED41-PadDO)") (class "Default")
      (node (ref "LED41") (pin "DO") (pinfunction "DO_DO") (pintype "output"))
      (node (ref "LED42") (pin "DI") (pinfunction "DI_DI") (pintype "input"))
    )
    (net (code "45") (name "Net-(LED42-PadDO)") (class "Default")
      (node (ref "LED42") (pin "DO") (pinfunction "DO_DO") (pintype "output"))
      (node (ref "LED43") (pin "DI") (pinfunction "DI_DI") (pintype "input"))
    )
    (net (code "46") (name "Net-(LED43-PadDO)") (class "Default")
      (node (ref "LED43") (pin "DO") (pinfunction "DO_DO") (pintype "output"))
      (node (ref "LED44") (pin "DI") (pinfunction "DI_DI") (pintype "input"))
    )
    (net (code "47") (name "Net-(LED44-PadDO)") (class "Default")
      (node (ref "LED44") (pin "DO") (pinfunction "DO_DO") (pintype "output"))
      (node (ref "LED45") (pin "DI") (pinfunction "DI_DI") (pintype "input"))
    )
    (net (code "48") (name "Net-(LED45-PadDO)") (class "Default")
      (node (ref "LED45") (pin "DO") (pinfunction "DO_DO") (pintype "output"))
      (node (ref "LED46") (pin "DI") (pinfunction "DI_DI") (pintype "input"))
    )
    (net (code "49") (name "Net-(LED46-PadDO)") (class "Default")
      (node (ref "LED46") (pin "DO") (pinfunction "DO_DO") (pintype "output"))
      (node (ref "LED47") (pin "DI") (pinfunction "DI_DI") (pintype "input"))
    )
    (net (code "50") (name "Net-(LED47-PadDO)") (class "Default")
      (node (ref "LED47") (pin "DO") (pinfunction "DO_DO") (pintype "output"))
      (node (ref "LED48") (pin "DI") (pinfunction "DI_DI") (pintype "input"))
    )
    (net (code "51") (name "Net-(LED48-PadDO)") (class "Default")
      (node (ref "LED48") (pin "DO") (pinfunction "DO_DO") (pintype "output"))
      (node (ref "LED49") (pin "DI") (pinfunction "DI_DI") (pintype "input"))
    )
    (net (code "52") (name "Net-(LED49-PadDO)") (class "Default")
      (node (ref "LED49") (pin "DO") (pinfunction "DO_DO") (pintype "output"))
      (node (ref "LED50") (pin "DI") (pinfunction "DI_DI") (pintype "input"))
    )
    (net (code "53") (name "Net-(LED50-PadDO)") (class "Default")
      (node (ref "LED50") (pin "DO") (pinfunction "DO_DO") (pintype "output"))
      (node (ref "LED51") (pin "DI") (pinfunction "DI_DI") (pintype "input"))
    )
    (net (code "54") (name "Net-(LED51-PadDO)") (class "Default")
      (node (ref "LED51") (pin "DO") (pinfunction "DO_DO") (pintype "output"))
      (node (ref "LED52") (pin "DI") (pinfunction "DI_DI") (pintype "input"))
    )
    (net (code "55") (name "Net-(LED52-PadDO)") (class "Default")
      (node (ref "LED52") (pin "DO") (pinfunction "DO_DO") (pintype "output"))
      (node (ref "LED53") (pin "DI") (pinfunction "DI_DI") (pintype "input"))
    )
    (net (code "56") (name "Net-(LED53-PadDO)") (class "Default")
      (node (ref "LED53") (pin "DO") (pinfunction "DO_DO") (pintype "output"))
      (node (ref "LED54") (pin "DI") (pinfunction "DI_DI") (pintype "input"))
    )
    (net (code "57") (name "Net-(LED54-PadDO)") (class "Default")
      (node (ref "LED54") (pin "DO") (pinfunction "DO_DO") (pintype "output"))
      (node (ref "LED55") (pin "DI") (pinfunction "DI_DI") (pintype "input"))
    )
    (net (code "58") (name "Net-(LED55-PadDO)") (class "Default")
      (node (ref "LED55") (pin "DO") (pinfunction "DO_DO") (pintype "output"))
      (node (ref "LED56") (pin "DI") (pinfunction "DI_DI") (pintype "input"))
    )
    (net (code "59") (name "Net-(LED56-PadDO)") (class "Default")
      (node (ref "LED56") (pin "DO") (pinfunction "DO_DO") (pintype "output"))
      (node (ref "LED57") (pin "DI") (pinfunction "DI_DI") (pintype "input"))
    )
    (net (code "60") (name "Net-(LED57-PadDO)") (class "Default")
      (node (ref "LED57") (pin "DO") (pinfunction "DO_DO") (pintype "output"))
      (node (ref "LED58") (pin "DI") (pinfunction "DI_DI") (pintype "input"))
    )
    (net (code "61") (name "Net-(LED58-PadDO)") (class "Default")
      (node (ref "LED58") (pin "DO") (pinfunction "DO_DO") (pintype "output"))
      (node (ref "LED59") (pin "DI") (pinfunction "DI_DI") (pintype "input"))
    )
    (net (code "62") (name "Net-(LED59-PadDO)") (class "Default")
      (node (ref "LED59") (pin "DO") (pinfunction "DO_DO") (pintype "output"))
      (node (ref "LED60") (pin "DI") (pinfunction "DI_DI") (pintype "input"))
    )
    (net (code "63") (name "Net-(LED60-PadDO)") (class "Default")
      (node (ref "LED60") (pin "DO") (pinfunction "DO_DO") (pintype "output"))
      (node (ref "LED61") (pin "DI") (pinfunction "DI_DI") (pintype "input"))
    )
    (net (code "64") (name "Net-(LED61-PadDO)") (class "Default")
      (node (ref "LED61") (pin "DO") (pinfunction "DO_DO") (pintype "output"))
      (node (ref "LED62") (pin "DI") (pinfunction "DI_DI") (pintype "input"))
    )
    (net (code "65") (name "Net-(LED62-PadDO)") (class "Default")
      (node (ref "LED62") (pin "DO") (pinfunction "DO_DO") (pintype "output"))
      (node (ref "LED63") (pin "DI") (pinfunction "DI_DI") (pintype "input"))
    )
    (net (code "66") (name "Net-(LED63-PadDO)") (class "Default")
      (node (ref "LED63") (pin "DO") (pinfunction "DO_DO") (pintype "output"))
      (node (ref "LED64") (pin "DI") (pinfunction "DI_DI") (pintype "input"))
    )
    (net (code "67") (name "Net-(LED64-PadDO)") (class "Default")
      (node (ref "LED64") (pin "DO") (pinfunction "DO_DO") (pintype "output"))
      (node (ref "LED65") (pin "DI") (pinfunction "DI_DI") (pintype "input"))
    )
    (net (code "68") (name "Net-(LED65-PadDO)") (class "Default")
      (node (ref "LED65") (pin "DO") (pinfunction "DO_DO") (pintype "output"))
      (node (ref "LED66") (pin "DI") (pinfunction "DI_DI") (pintype "input"))
    )
    (net (code "69") (name "Net-(LED66-PadDO)") (class "Default")
      (node (ref "LED66") (pin "DO") (pinfunction "DO_DO") (pintype "output"))
      (node (ref "LED67") (pin "DI") (pinfunction "DI_DI") (pintype "input"))
    )
    (net (code "70") (name "Net-(LED67-PadDO)") (class "Default")
      (node (ref "LED67") (pin "DO") (pinfunction "DO_DO") (pintype "output"))
      (node (ref "LED68") (pin "DI") (pinfunction "DI_DI") (pintype "input"))
    )
    (net (code "71") (name "Net-(LED68-PadDO)") (class "Default")
      (node (ref "LED68") (pin "DO") (pinfunction "DO_DO") (pintype "output"))
      (node (ref "LED69") (pin "DI") (pinfunction "DI_DI") (pintype "input"))
    )
    (net (code "72") (name "Net-(LED69-PadDO)") (class "Default")
      (node (ref "LED69") (pin "DO") (pinfunction "DO_DO") (pintype "output"))
      (node (ref "LED70") (pin "DI") (pinfunction "DI_DI") (pintype "input"))
    )
    (net (code "73") (name "Net-(LED70-PadDO)") (class "Default")
      (node (ref "LED70") (pin "DO") (pinfunction "DO_DO") (pintype "output"))
      (node (ref "LED71") (pin "DI") (pinfunction "DI_DI") (pintype "input"))
    )
    (net (code "74") (name "Net-(LED71-PadDO)") (class "Default")
      (node (ref "LED71") (pin "DO") (pinfunction "DO_DO") (pintype "output"))
      (node (ref "LED72") (pin "DI") (pinfunction "DI_DI") (pintype "input"))
    )
    (net (code "75") (name "Net-(LED72-PadDO)") (class "Default")
      (node (ref "LED72") (pin "DO") (pinfunction "DO_DO") (pintype "output"))
      (node (ref "LED73") (pin "DI") (pinfunction "DI_DI") (pintype "input"))
    )
    (net (code "76") (name "Net-(LED73-PadDO)") (class "Default")
      (node (ref "LED73") (pin "DO") (pinfunction "DO_DO") (pintype "output"))
      (node (ref "LED74") (pin "DI") (pinfunction "DI_DI") (pintype "input"))
    )
    (net (code "77") (name "Net-(LED74-PadDO)") (class "Default")
      (node (ref "LED74") (pin "DO") (pinfunction "DO_DO") (pintype "output"))
      (node (ref "LED75") (pin "DI") (pinfunction "DI_DI") (pintype "input"))
    )
    (net (code "78") (name "Net-(LED75-PadDO)") (class "Default")
      (node (ref "LED75") (pin "DO") (pinfunction "DO_DO") (pintype "output"))
      (node (ref "LED76") (pin "DI") (pinfunction "DI_DI") (pintype "input"))
    )
    (net (code "79") (name "Net-(LED76-PadDO)") (class "Default")
      (node (ref "LED76") (pin "DO") (pinfunction "DO_DO") (pintype "output"))
      (node (ref "LED77") (pin "DI") (pinfunction "DI_DI") (pintype "input"))
    )
    (net (code "80") (name "Net-(LED77-PadDO)") (class "Default")
      (node (ref "LED77") (pin "DO") (pinfunction "DO_DO") (pintype "output"))
      (node (ref "LED78") (pin "DI") (pinfunction "DI_DI") (pintype "input"))
    )
    (net (code "81") (name "Net-(LED78-PadDO)") (class "Default")
      (node (ref "LED78") (pin "DO") (pinfunction "DO_DO") (pintype "output"))
      (node (ref "LED79") (pin "DI") (pinfunction "DI_DI") (pintype "input"))
    )
    (net (code "82") (name "Net-(LED79-PadDO)") (class "Default")
      (node (ref "LED79") (pin "DO") (pinfunction "DO_DO") (pintype "output"))
      (node (ref "LED80") (pin "DI") (pinfunction "DI_DI") (pintype "input"))
    )
    (net (code "83") (name "Net-(LED80-PadDO)") (class "Default")
      (node (ref "LED80") (pin "DO") (pinfunction "DO_DO") (pintype "output"))
      (node (ref "LED81") (pin "DI") (pinfunction "DI_DI") (pintype "input"))
    )
    (net (code "84") (name "Net-(LED81-PadDO)") (class "Default")
      (node (ref "LED81") (pin "DO") (pinfunction "DO_DO") (pintype "output"))
      (node (ref "LED82") (pin "DI") (pinfunction "DI_DI") (pintype "input"))
    )
    (net (code "85") (name "Net-(LED82-PadDO)") (class "Default")
      (node (ref "LED82") (pin "DO") (pinfunction "DO_DO") (pintype "output"))
      (node (ref "LED83") (pin "DI") (pinfunction "DI_DI") (pintype "input"))
    )
    (net (code "86") (name "Net-(LED83-PadDO)") (class "Default")
      (node (ref "LED83") (pin "DO") (pinfunction "DO_DO") (pintype "output"))
      (node (ref "LED84") (pin "DI") (pinfunction "DI_DI") (pintype "input"))
    )
    (net (code "87") (name "Net-(LED84-PadDO)") (class "Default")
      (node (ref "LED84") (pin "DO") (pinfunction "DO_DO") (pintype "output"))
      (node (ref "LED85") (pin "DI") (pinfunction "DI_DI") (pintype "input"))
    )
    (net (code "88") (name "Net-(LED85-PadDO)") (class "Default")
      (node (ref "LED85") (pin "DO") (pinfunction "DO_DO") (pintype "output"))
      (node (ref "LED86") (pin "DI") (pinfunction "DI_DI") (pintype "input"))
    )
    (net (code "89") (name "Net-(LED86-PadDO)") (class "Default")
      (node (ref "LED86") (pin "DO") (pinfunction "DO_DO") (pintype "output"))
      (node (ref "LED87") (pin "DI") (pinfunction "DI_DI") (pintype "input"))
    )
    (net (code "90") (name "Net-(LED87-PadDO)") (class "Default")
      (node (ref "LED87") (pin "DO") (pinfunction "DO_DO") (pintype "output"))
      (node (ref "LED88") (pin "DI") (pinfunction "DI_DI") (pintype "input"))
    )
    (net (code "91") (name "Net-(LED88-PadDO)") (class "Default")
      (node (ref "LED88") (pin "DO") (pinfunction "DO_DO") (pintype "output"))
      (node (ref "LED89") (pin "DI") (pinfunction "DI_DI") (pintype "input"))
    )
    (net (code "92") (name "Net-(LED89-PadDO)") (class "Default")
      (node (ref "LED89") (pin "DO") (pinfunction "DO_DO") (pintype "output"))
      (node (ref "LED90") (pin "DI") (pinfunction "DI_DI") (pintype "input"))
    )
    (net (code "93") (name "Net-(LED90-PadDO)") (class "Default")
      (node (ref "LED90") (pin "DO") (pinfunction "DO_DO") (pintype "output"))
      (node (ref "LED91") (pin "DI") (pinfunction "DI_DI") (pintype "input"))
    )
    (net (code "94") (name "Net-(LED91-PadDO)") (class "Default")
      (node (ref "LED91") (pin "DO") (pinfunction "DO_DO") (pintype "output"))
      (node (ref "LED92") (pin "DI") (pinfunction "DI_DI") (pintype "input"))
    )
    (net (code "95") (name "Net-(LED92-PadDO)") (class "Default")
      (node (ref "LED92") (pin "DO") (pinfunction "DO_DO") (pintype "output"))
      (node (ref "LED93") (pin "DI") (pinfunction "DI_DI") (pintype "input"))
    )
    (net (code "96") (name "Net-(LED93-PadDO)") (class "Default")
      (node (ref "LED93") (pin "DO") (pinfunction "DO_DO") (pintype "output"))
      (node (ref "LED94") (pin "DI") (pinfunction "DI_DI") (pintype "input"))
    )
    (net (code "97") (name "Net-(LED94-PadDO)") (class "Default")
      (node (ref "LED94") (pin "DO") (pinfunction "DO_DO") (pintype "output"))
      (node (ref "LED95") (pin "DI") (pinfunction "DI_DI") (pintype "input"))
    )
    (net (code "98") (name "Net-(LED95-PadDO)") (class "Default")
      (node (ref "LED95") (pin "DO") (pinfunction "DO_DO") (pintype "output"))
      (node (ref "LED96") (pin "DI") (pinfunction "DI_DI") (pintype "input"))
    )
    (net (code "99") (name "Net-(LED96-PadDO)") (class "Default")
      (node (ref "LED96") (pin "DO") (pinfunction "DO_DO") (pintype "output"))
      (node (ref "LED97") (pin "DI") (pinfunction "DI_DI") (pintype "input"))
    )
    (net (code "100") (name "Net-(LED97-PadDO)") (class "Default")
      (node (ref "LED97") (pin "DO") (pinfunction "DO_DO") (pintype "output"))
      (node (ref "LED98") (pin "DI") (pinfunction "DI_DI") (pintype "input"))
    )
    (net (code "101") (name "Net-(LED98-PadDO)") (class "Default")
      (node (ref "LED98") (pin "DO") (pinfunction "DO_DO") (pintype "output"))
      (node (ref "LED99") (pin "DI") (pinfunction "DI_DI") (pintype "input"))
    )
    (net (code "102") (name "Net-(LED100-PadDI)") (class "Default")
      (node (ref "LED100") (pin "DI") (pinfunction "DI_DI") (pintype "input"))
      (node (ref "LED99") (pin "DO") (pinfunction "DO_DO") (pintype "output"))
    )
    (net (code "103") (name "unconnected-(LED100-PadDO)") (class "Default")
      (node (ref "LED100") (pin "DO") (pinfunction "DO_DO") (pintype "output"))
    )
  )
)
